# AtoVproject_16n_ALPS_V1_4_NL.net
KiCad netlist of a schematic drawn in EAGLE
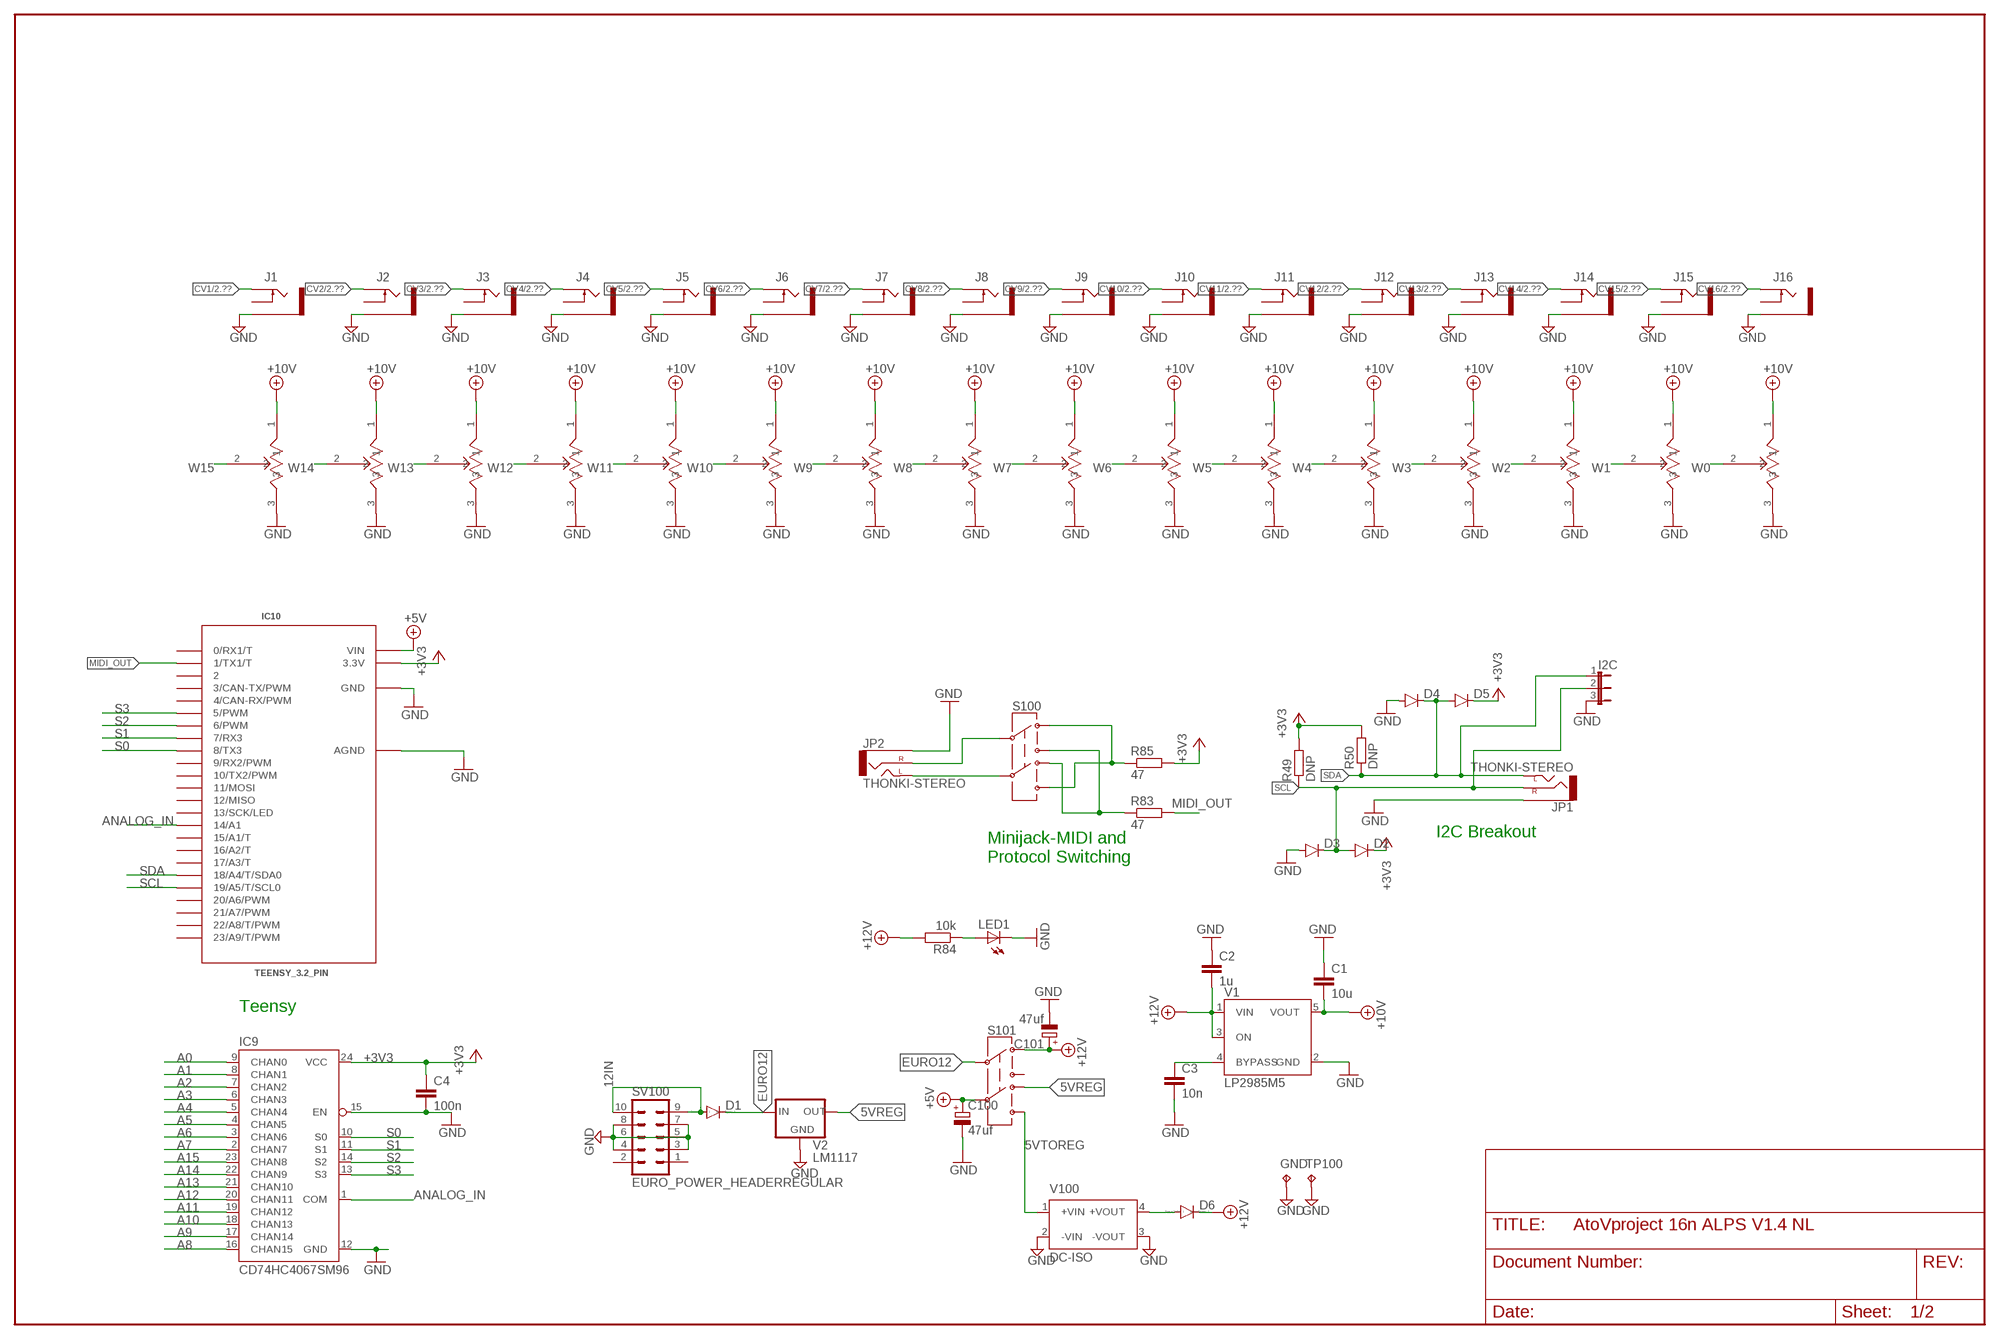
[diagram p0: schematic, sheet 1]
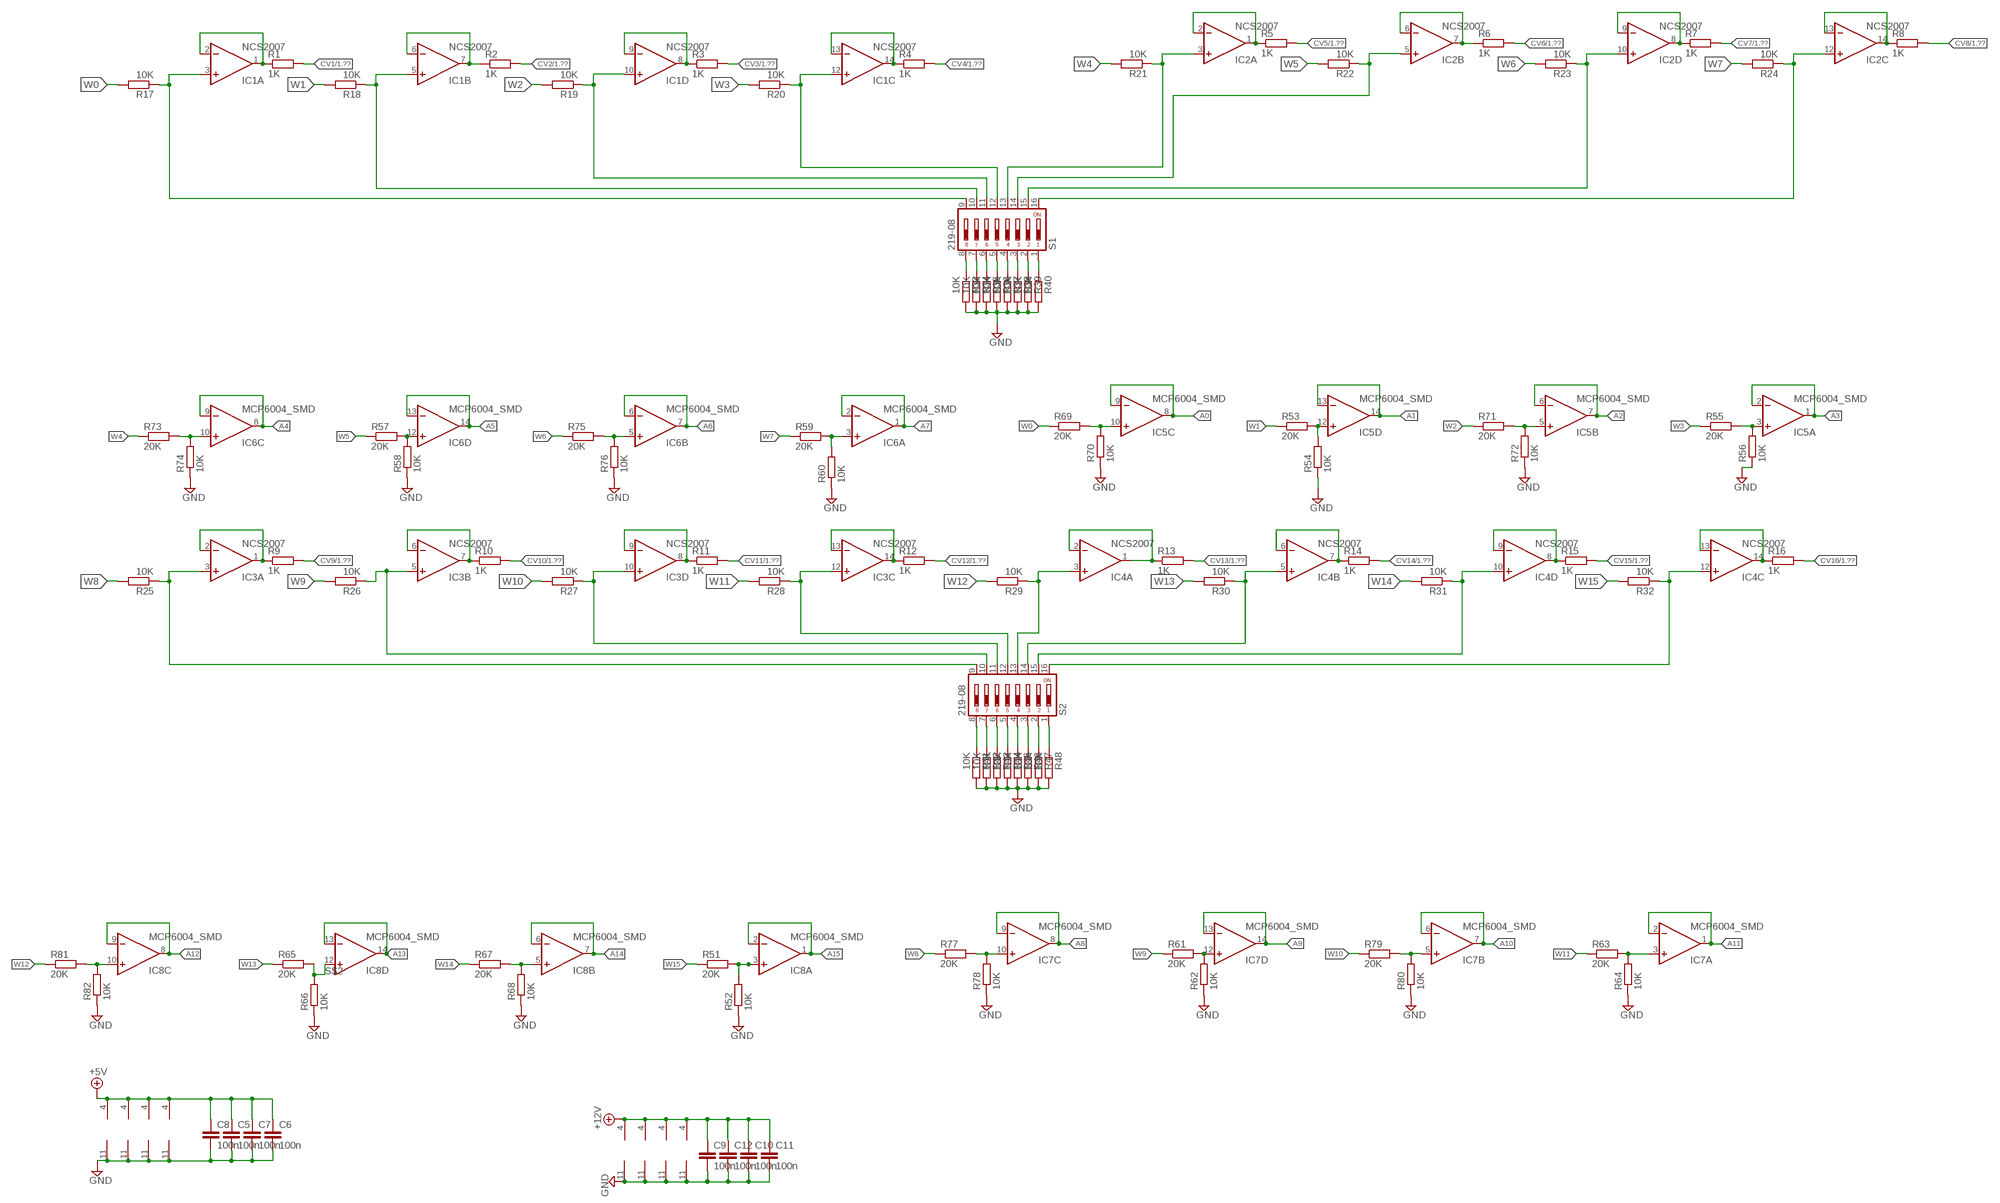
[diagram p1: schematic, sheet 2]

(export (version "E")
  (design (tool "Eeschema 10.0.6"))
  (components
    (comp (ref "C1")
      (value "10u")
      (footprint "eagle-import:C0805")
      (libsource (lib "eagle-import") (part "C-EUC0805"))
    )
    (comp (ref "C2")
      (value "1u")
      (footprint "eagle-import:C0805")
      (libsource (lib "eagle-import") (part "C-EUC0805"))
    )
    (comp (ref "C3")
      (value "10n")
      (footprint "eagle-import:C0805")
      (libsource (lib "eagle-import") (part "C-EUC0805"))
    )
    (comp (ref "C4")
      (value "100n")
      (footprint "eagle-import:C0805")
      (libsource (lib "eagle-import") (part "C-EUC0805"))
    )
    (comp (ref "C100")
      (value "47uf")
      (footprint "eagle-import:E2,5-6")
      (libsource (lib "eagle-import") (part "CPOL-EUE2.5-6"))
    )
    (comp (ref "C101")
      (value "47uf")
      (footprint "eagle-import:E2,5-6")
      (libsource (lib "eagle-import") (part "CPOL-EUE2.5-6"))
    )
    (comp (ref "D1")
      (value "DIODE-SOD123")
      (footprint "eagle-import:SOD123")
      (libsource (lib "eagle-import") (part "DIODE-SOD123"))
    )
    (comp (ref "D2")
      (value "DIODESOD123")
      (footprint "eagle-import:SOD-123")
      (libsource (lib "eagle-import") (part "DIODESOD123"))
    )
    (comp (ref "D3")
      (value "DIODESOD123")
      (footprint "eagle-import:SOD-123")
      (libsource (lib "eagle-import") (part "DIODESOD123"))
    )
    (comp (ref "D4")
      (value "DIODESOD123")
      (footprint "eagle-import:SOD-123")
      (libsource (lib "eagle-import") (part "DIODESOD123"))
    )
    (comp (ref "D5")
      (value "DIODESOD123")
      (footprint "eagle-import:SOD-123")
      (libsource (lib "eagle-import") (part "DIODESOD123"))
    )
    (comp (ref "D6")
      (value "DIODE-SOD123")
      (footprint "eagle-import:SOD123")
      (libsource (lib "eagle-import") (part "DIODE-SOD123"))
    )
    (comp (ref "GND")
      (value "TPPAD1-17")
      (footprint "eagle-import:P1-17")
      (libsource (lib "eagle-import") (part "TPPAD1-17"))
    )
    (comp (ref "I2C")
      (value "JP2E")
      (footprint "eagle-import:JP2")
      (libsource (lib "eagle-import") (part "JP2E"))
    )
    (comp (ref "IC9")
      (value "CD74HC4067SM96")
      (footprint "eagle-import:SOIC127P1030X265-24")
      (libsource (lib "eagle-import") (part "744067SO24"))
    )
    (comp (ref "IC10")
      (value "TEENSY_3.2_PIN")
      (footprint "eagle-import:TEENSY_3_AND_LC_SERIES_BOARDS_V1.4_TEENSY_3.0-3.2&LC_DIL")
      (libsource (lib "eagle-import") (part "TEENSY_3.2_PIN"))
    )
    (comp (ref "J1")
      (value "THONKICONN")
      (footprint "eagle-import:WQP-PJ301M-12JACK-BANANA")
      (libsource (lib "eagle-import") (part "THONKICONN"))
    )
    (comp (ref "J2")
      (value "THONKICONN")
      (footprint "eagle-import:WQP-PJ301M-12JACK-BANANA")
      (libsource (lib "eagle-import") (part "THONKICONN"))
    )
    (comp (ref "J3")
      (value "THONKICONN")
      (footprint "eagle-import:WQP-PJ301M-12JACK-BANANA")
      (libsource (lib "eagle-import") (part "THONKICONN"))
    )
    (comp (ref "J4")
      (value "THONKICONN")
      (footprint "eagle-import:WQP-PJ301M-12JACK-BANANA")
      (libsource (lib "eagle-import") (part "THONKICONN"))
    )
    (comp (ref "J5")
      (value "THONKICONN")
      (footprint "eagle-import:WQP-PJ301M-12JACK-BANANA")
      (libsource (lib "eagle-import") (part "THONKICONN"))
    )
    (comp (ref "J6")
      (value "THONKICONN")
      (footprint "eagle-import:WQP-PJ301M-12JACK-BANANA")
      (libsource (lib "eagle-import") (part "THONKICONN"))
    )
    (comp (ref "J7")
      (value "THONKICONN")
      (footprint "eagle-import:WQP-PJ301M-12JACK-BANANA")
      (libsource (lib "eagle-import") (part "THONKICONN"))
    )
    (comp (ref "J8")
      (value "THONKICONN")
      (footprint "eagle-import:WQP-PJ301M-12JACK-BANANA")
      (libsource (lib "eagle-import") (part "THONKICONN"))
    )
    (comp (ref "J9")
      (value "THONKICONN")
      (footprint "eagle-import:WQP-PJ301M-12JACK-BANANA")
      (libsource (lib "eagle-import") (part "THONKICONN"))
    )
    (comp (ref "J10")
      (value "THONKICONN")
      (footprint "eagle-import:WQP-PJ301M-12JACK-BANANA")
      (libsource (lib "eagle-import") (part "THONKICONN"))
    )
    (comp (ref "J11")
      (value "THONKICONN")
      (footprint "eagle-import:WQP-PJ301M-12JACK-BANANA")
      (libsource (lib "eagle-import") (part "THONKICONN"))
    )
    (comp (ref "J12")
      (value "THONKICONN")
      (footprint "eagle-import:WQP-PJ301M-12JACK-BANANA")
      (libsource (lib "eagle-import") (part "THONKICONN"))
    )
    (comp (ref "J13")
      (value "THONKICONN")
      (footprint "eagle-import:WQP-PJ301M-12JACK-BANANA")
      (libsource (lib "eagle-import") (part "THONKICONN"))
    )
    (comp (ref "J14")
      (value "THONKICONN")
      (footprint "eagle-import:WQP-PJ301M-12JACK-BANANA")
      (libsource (lib "eagle-import") (part "THONKICONN"))
    )
    (comp (ref "J15")
      (value "THONKICONN")
      (footprint "eagle-import:WQP-PJ301M-12JACK-BANANA")
      (libsource (lib "eagle-import") (part "THONKICONN"))
    )
    (comp (ref "J16")
      (value "THONKICONN")
      (footprint "eagle-import:WQP-PJ301M-12JACK-BANANA")
      (libsource (lib "eagle-import") (part "THONKICONN"))
    )
    (comp (ref "JP1")
      (value "THONKI-STEREO")
      (footprint "eagle-import:WQP-PJ366ST_JACK")
      (libsource (lib "eagle-import") (part "THONKI-STEREO"))
    )
    (comp (ref "JP2")
      (value "THONKI-STEREO")
      (footprint "eagle-import:WQP-PJ366ST_JACK")
      (libsource (lib "eagle-import") (part "THONKI-STEREO"))
    )
    (comp (ref "LED1")
      (value "LED")
      (footprint "eagle-import:LED3MM")
      (libsource (lib "eagle-import") (part "LED"))
    )
    (comp (ref "R49")
      (value "DNP")
      (footprint "eagle-import:R0805")
      (libsource (lib "eagle-import") (part "R-EU_R0805"))
    )
    (comp (ref "R50")
      (value "DNP")
      (footprint "eagle-import:R0805")
      (libsource (lib "eagle-import") (part "R-EU_R0805"))
    )
    (comp (ref "R83")
      (value "47")
      (footprint "eagle-import:R0805")
      (libsource (lib "eagle-import") (part "R-EU_R0805"))
    )
    (comp (ref "R84")
      (value "10k")
      (footprint "eagle-import:R0805")
      (libsource (lib "eagle-import") (part "R-EU_R0805"))
    )
    (comp (ref "R85")
      (value "47")
      (footprint "eagle-import:R0805")
      (libsource (lib "eagle-import") (part "R-EU_R0805"))
    )
    (comp (ref "S100")
      (value "SWITCH-DPDTEG2211")
      (footprint "eagle-import:EG2211")
      (libsource (lib "eagle-import") (part "SWITCH-DPDTEG2211"))
    )
    (comp (ref "S101")
      (value "SWITCH-DPDTEG2211")
      (footprint "eagle-import:EG2211")
      (libsource (lib "eagle-import") (part "SWITCH-DPDTEG2211"))
    )
    (comp (ref "SV100")
      (value "EURO_POWER_HEADERREGULAR")
      (footprint "eagle-import:EURO_POWER_HEADER")
      (libsource (lib "eagle-import") (part "EURO_POWER_HEADERREGULAR"))
    )
    (comp (ref "TP100")
      (value "TPPAD1-17")
      (footprint "eagle-import:P1-17")
      (libsource (lib "eagle-import") (part "TPPAD1-17"))
    )
    (comp (ref "U$1")
      (value "SLIDERSALPS-60MM")
      (footprint "eagle-import:MONOME_RS6011SP600")
      (libsource (lib "eagle-import") (part "SLIDERSALPS-60MM"))
    )
    (comp (ref "U$2")
      (value "SLIDERSALPS-60MM")
      (footprint "eagle-import:MONOME_RS6011SP600")
      (libsource (lib "eagle-import") (part "SLIDERSALPS-60MM"))
    )
    (comp (ref "U$3")
      (value "SLIDERSALPS-60MM")
      (footprint "eagle-import:MONOME_RS6011SP600")
      (libsource (lib "eagle-import") (part "SLIDERSALPS-60MM"))
    )
    (comp (ref "U$4")
      (value "SLIDERSALPS-60MM")
      (footprint "eagle-import:MONOME_RS6011SP600")
      (libsource (lib "eagle-import") (part "SLIDERSALPS-60MM"))
    )
    (comp (ref "U$5")
      (value "SLIDERSALPS-60MM")
      (footprint "eagle-import:MONOME_RS6011SP600")
      (libsource (lib "eagle-import") (part "SLIDERSALPS-60MM"))
    )
    (comp (ref "U$6")
      (value "SLIDERSALPS-60MM")
      (footprint "eagle-import:MONOME_RS6011SP600")
      (libsource (lib "eagle-import") (part "SLIDERSALPS-60MM"))
    )
    (comp (ref "U$7")
      (value "SLIDERSALPS-60MM")
      (footprint "eagle-import:MONOME_RS6011SP600")
      (libsource (lib "eagle-import") (part "SLIDERSALPS-60MM"))
    )
    (comp (ref "U$8")
      (value "SLIDERSALPS-60MM")
      (footprint "eagle-import:MONOME_RS6011SP600")
      (libsource (lib "eagle-import") (part "SLIDERSALPS-60MM"))
    )
    (comp (ref "U$9")
      (value "SLIDERSALPS-60MM")
      (footprint "eagle-import:MONOME_RS6011SP600")
      (libsource (lib "eagle-import") (part "SLIDERSALPS-60MM"))
    )
    (comp (ref "U$10")
      (value "SLIDERSALPS-60MM")
      (footprint "eagle-import:MONOME_RS6011SP600")
      (libsource (lib "eagle-import") (part "SLIDERSALPS-60MM"))
    )
    (comp (ref "U$11")
      (value "SLIDERSALPS-60MM")
      (footprint "eagle-import:MONOME_RS6011SP600")
      (libsource (lib "eagle-import") (part "SLIDERSALPS-60MM"))
    )
    (comp (ref "U$12")
      (value "SLIDERSALPS-60MM")
      (footprint "eagle-import:MONOME_RS6011SP600")
      (libsource (lib "eagle-import") (part "SLIDERSALPS-60MM"))
    )
    (comp (ref "U$13")
      (value "SLIDERSALPS-60MM")
      (footprint "eagle-import:MONOME_RS6011SP600")
      (libsource (lib "eagle-import") (part "SLIDERSALPS-60MM"))
    )
    (comp (ref "U$14")
      (value "SLIDERSALPS-60MM")
      (footprint "eagle-import:MONOME_RS6011SP600")
      (libsource (lib "eagle-import") (part "SLIDERSALPS-60MM"))
    )
    (comp (ref "U$15")
      (value "SLIDERSALPS-60MM")
      (footprint "eagle-import:MONOME_RS6011SP600")
      (libsource (lib "eagle-import") (part "SLIDERSALPS-60MM"))
    )
    (comp (ref "U$16")
      (value "SLIDERSALPS-60MM")
      (footprint "eagle-import:MONOME_RS6011SP600")
      (libsource (lib "eagle-import") (part "SLIDERSALPS-60MM"))
    )
    (comp (ref "V1")
      (value "LP2985M5")
      (footprint "eagle-import:SOT23-5")
      (libsource (lib "eagle-import") (part "LP2985M5"))
    )
    (comp (ref "V2")
      (value "LM1117")
      (footprint "eagle-import:SOT223")
      (libsource (lib "eagle-import") (part "LM1117"))
    )
    (comp (ref "V100")
      (value "DC-ISO")
      (footprint "eagle-import:TMA")
      (libsource (lib "eagle-import") (part "DC-ISO"))
    )
    (comp (ref "C5")
      (value "100n")
      (footprint "eagle-import:C0805")
      (libsource (lib "eagle-import") (part "C-EUC0805"))
    )
    (comp (ref "C6")
      (value "100n")
      (footprint "eagle-import:C0805")
      (libsource (lib "eagle-import") (part "C-EUC0805"))
    )
    (comp (ref "C7")
      (value "100n")
      (footprint "eagle-import:C0805")
      (libsource (lib "eagle-import") (part "C-EUC0805"))
    )
    (comp (ref "C8")
      (value "100n")
      (footprint "eagle-import:C0805")
      (libsource (lib "eagle-import") (part "C-EUC0805"))
    )
    (comp (ref "C9")
      (value "100n")
      (footprint "eagle-import:C0805")
      (libsource (lib "eagle-import") (part "C-EUC0805"))
    )
    (comp (ref "C10")
      (value "100n")
      (footprint "eagle-import:C0805")
      (libsource (lib "eagle-import") (part "C-EUC0805"))
    )
    (comp (ref "C11")
      (value "100n")
      (footprint "eagle-import:C0805")
      (libsource (lib "eagle-import") (part "C-EUC0805"))
    )
    (comp (ref "C12")
      (value "100n")
      (footprint "eagle-import:C0805")
      (libsource (lib "eagle-import") (part "C-EUC0805"))
    )
    (comp (ref "IC1")
      (value "NCS2007")
      (footprint "eagle-import:SO14")
      (libsource (lib "eagle-import") (part "TL074"))
    )
    (comp (ref "IC2")
      (value "NCS2007")
      (footprint "eagle-import:SO14")
      (libsource (lib "eagle-import") (part "TL074"))
    )
    (comp (ref "IC3")
      (value "NCS2007")
      (footprint "eagle-import:SO14")
      (libsource (lib "eagle-import") (part "TL074"))
    )
    (comp (ref "IC4")
      (value "NCS2007")
      (footprint "eagle-import:SO14")
      (libsource (lib "eagle-import") (part "TL074"))
    )
    (comp (ref "IC5")
      (value "MCP6004_SMD")
      (footprint "eagle-import:SO14")
      (libsource (lib "eagle-import") (part "MCP6004_SMD"))
    )
    (comp (ref "IC6")
      (value "MCP6004_SMD")
      (footprint "eagle-import:SO14")
      (libsource (lib "eagle-import") (part "MCP6004_SMD"))
    )
    (comp (ref "IC7")
      (value "MCP6004_SMD")
      (footprint "eagle-import:SO14")
      (libsource (lib "eagle-import") (part "MCP6004_SMD"))
    )
    (comp (ref "IC8")
      (value "MCP6004_SMD")
      (footprint "eagle-import:SO14")
      (libsource (lib "eagle-import") (part "MCP6004_SMD"))
    )
    (comp (ref "R1")
      (value "1K")
      (footprint "eagle-import:R0805")
      (libsource (lib "eagle-import") (part "R-EU_R0805"))
    )
    (comp (ref "R2")
      (value "1K")
      (footprint "eagle-import:R0805")
      (libsource (lib "eagle-import") (part "R-EU_R0805"))
    )
    (comp (ref "R3")
      (value "1K")
      (footprint "eagle-import:R0805")
      (libsource (lib "eagle-import") (part "R-EU_R0805"))
    )
    (comp (ref "R4")
      (value "1K")
      (footprint "eagle-import:R0805")
      (libsource (lib "eagle-import") (part "R-EU_R0805"))
    )
    (comp (ref "R5")
      (value "1K")
      (footprint "eagle-import:R0805")
      (libsource (lib "eagle-import") (part "R-EU_R0805"))
    )
    (comp (ref "R6")
      (value "1K")
      (footprint "eagle-import:R0805")
      (libsource (lib "eagle-import") (part "R-EU_R0805"))
    )
    (comp (ref "R7")
      (value "1K")
      (footprint "eagle-import:R0805")
      (libsource (lib "eagle-import") (part "R-EU_R0805"))
    )
    (comp (ref "R8")
      (value "1K")
      (footprint "eagle-import:R0805")
      (libsource (lib "eagle-import") (part "R-EU_R0805"))
    )
    (comp (ref "R9")
      (value "1K")
      (footprint "eagle-import:R0805")
      (libsource (lib "eagle-import") (part "R-EU_R0805"))
    )
    (comp (ref "R10")
      (value "1K")
      (footprint "eagle-import:R0805")
      (libsource (lib "eagle-import") (part "R-EU_R0805"))
    )
    (comp (ref "R11")
      (value "1K")
      (footprint "eagle-import:R0805")
      (libsource (lib "eagle-import") (part "R-EU_R0805"))
    )
    (comp (ref "R12")
      (value "1K")
      (footprint "eagle-import:R0805")
      (libsource (lib "eagle-import") (part "R-EU_R0805"))
    )
    (comp (ref "R13")
      (value "1K")
      (footprint "eagle-import:R0805")
      (libsource (lib "eagle-import") (part "R-EU_R0805"))
    )
    (comp (ref "R14")
      (value "1K")
      (footprint "eagle-import:R0805")
      (libsource (lib "eagle-import") (part "R-EU_R0805"))
    )
    (comp (ref "R15")
      (value "1K")
      (footprint "eagle-import:R0805")
      (libsource (lib "eagle-import") (part "R-EU_R0805"))
    )
    (comp (ref "R16")
      (value "1K")
      (footprint "eagle-import:R0805")
      (libsource (lib "eagle-import") (part "R-EU_R0805"))
    )
    (comp (ref "R17")
      (value "10K")
      (footprint "eagle-import:R0805")
      (libsource (lib "eagle-import") (part "R-EU_R0805"))
    )
    (comp (ref "R18")
      (value "10K")
      (footprint "eagle-import:R0805")
      (libsource (lib "eagle-import") (part "R-EU_R0805"))
    )
    (comp (ref "R19")
      (value "10K")
      (footprint "eagle-import:R0805")
      (libsource (lib "eagle-import") (part "R-EU_R0805"))
    )
    (comp (ref "R20")
      (value "10K")
      (footprint "eagle-import:R0805")
      (libsource (lib "eagle-import") (part "R-EU_R0805"))
    )
    (comp (ref "R21")
      (value "10K")
      (footprint "eagle-import:R0805")
      (libsource (lib "eagle-import") (part "R-EU_R0805"))
    )
    (comp (ref "R22")
      (value "10K")
      (footprint "eagle-import:R0805")
      (libsource (lib "eagle-import") (part "R-EU_R0805"))
    )
    (comp (ref "R23")
      (value "10K")
      (footprint "eagle-import:R0805")
      (libsource (lib "eagle-import") (part "R-EU_R0805"))
    )
    (comp (ref "R24")
      (value "10K")
      (footprint "eagle-import:R0805")
      (libsource (lib "eagle-import") (part "R-EU_R0805"))
    )
    (comp (ref "R25")
      (value "10K")
      (footprint "eagle-import:R0805")
      (libsource (lib "eagle-import") (part "R-EU_R0805"))
    )
    (comp (ref "R26")
      (value "10K")
      (footprint "eagle-import:R0805")
      (libsource (lib "eagle-import") (part "R-EU_R0805"))
    )
    (comp (ref "R27")
      (value "10K")
      (footprint "eagle-import:R0805")
      (libsource (lib "eagle-import") (part "R-EU_R0805"))
    )
    (comp (ref "R28")
      (value "10K")
      (footprint "eagle-import:R0805")
      (libsource (lib "eagle-import") (part "R-EU_R0805"))
    )
    (comp (ref "R29")
      (value "10K")
      (footprint "eagle-import:R0805")
      (libsource (lib "eagle-import") (part "R-EU_R0805"))
    )
    (comp (ref "R30")
      (value "10K")
      (footprint "eagle-import:R0805")
      (libsource (lib "eagle-import") (part "R-EU_R0805"))
    )
    (comp (ref "R31")
      (value "10K")
      (footprint "eagle-import:R0805")
      (libsource (lib "eagle-import") (part "R-EU_R0805"))
    )
    (comp (ref "R32")
      (value "10K")
      (footprint "eagle-import:R0805")
      (libsource (lib "eagle-import") (part "R-EU_R0805"))
    )
    (comp (ref "R33")
      (value "10K")
      (footprint "eagle-import:R0805")
      (libsource (lib "eagle-import") (part "R-EU_R0805"))
    )
    (comp (ref "R34")
      (value "10K")
      (footprint "eagle-import:R0805")
      (libsource (lib "eagle-import") (part "R-EU_R0805"))
    )
    (comp (ref "R35")
      (value "10K")
      (footprint "eagle-import:R0805")
      (libsource (lib "eagle-import") (part "R-EU_R0805"))
    )
    (comp (ref "R36")
      (value "10K")
      (footprint "eagle-import:R0805")
      (libsource (lib "eagle-import") (part "R-EU_R0805"))
    )
    (comp (ref "R37")
      (value "10K")
      (footprint "eagle-import:R0805")
      (libsource (lib "eagle-import") (part "R-EU_R0805"))
    )
    (comp (ref "R38")
      (value "10K")
      (footprint "eagle-import:R0805")
      (libsource (lib "eagle-import") (part "R-EU_R0805"))
    )
    (comp (ref "R39")
      (value "10K")
      (footprint "eagle-import:R0805")
      (libsource (lib "eagle-import") (part "R-EU_R0805"))
    )
    (comp (ref "R40")
      (value "10K")
      (footprint "eagle-import:R0805")
      (libsource (lib "eagle-import") (part "R-EU_R0805"))
    )
    (comp (ref "R41")
      (value "10K")
      (footprint "eagle-import:R0805")
      (libsource (lib "eagle-import") (part "R-EU_R0805"))
    )
    (comp (ref "R42")
      (value "10K")
      (footprint "eagle-import:R0805")
      (libsource (lib "eagle-import") (part "R-EU_R0805"))
    )
    (comp (ref "R43")
      (value "10K")
      (footprint "eagle-import:R0805")
      (libsource (lib "eagle-import") (part "R-EU_R0805"))
    )
    (comp (ref "R44")
      (value "10K")
      (footprint "eagle-import:R0805")
      (libsource (lib "eagle-import") (part "R-EU_R0805"))
    )
    (comp (ref "R45")
      (value "10K")
      (footprint "eagle-import:R0805")
      (libsource (lib "eagle-import") (part "R-EU_R0805"))
    )
    (comp (ref "R46")
      (value "10K")
      (footprint "eagle-import:R0805")
      (libsource (lib "eagle-import") (part "R-EU_R0805"))
    )
    (comp (ref "R47")
      (value "10K")
      (footprint "eagle-import:R0805")
      (libsource (lib "eagle-import") (part "R-EU_R0805"))
    )
    (comp (ref "R48")
      (value "10K")
      (footprint "eagle-import:R0805")
      (libsource (lib "eagle-import") (part "R-EU_R0805"))
    )
    (comp (ref "R51")
      (value "20K")
      (footprint "eagle-import:R0805")
      (libsource (lib "eagle-import") (part "R-EU_R0805"))
    )
    (comp (ref "R52")
      (value "10K")
      (footprint "eagle-import:R0805")
      (libsource (lib "eagle-import") (part "R-EU_R0805"))
    )
    (comp (ref "R53")
      (value "20K")
      (footprint "eagle-import:R0805")
      (libsource (lib "eagle-import") (part "R-EU_R0805"))
    )
    (comp (ref "R54")
      (value "10K")
      (footprint "eagle-import:R0805")
      (libsource (lib "eagle-import") (part "R-EU_R0805"))
    )
    (comp (ref "R55")
      (value "20K")
      (footprint "eagle-import:R0805")
      (libsource (lib "eagle-import") (part "R-EU_R0805"))
    )
    (comp (ref "R56")
      (value "10K")
      (footprint "eagle-import:R0805")
      (libsource (lib "eagle-import") (part "R-EU_R0805"))
    )
    (comp (ref "R57")
      (value "20K")
      (footprint "eagle-import:R0805")
      (libsource (lib "eagle-import") (part "R-EU_R0805"))
    )
    (comp (ref "R58")
      (value "10K")
      (footprint "eagle-import:R0805")
      (libsource (lib "eagle-import") (part "R-EU_R0805"))
    )
    (comp (ref "R59")
      (value "20K")
      (footprint "eagle-import:R0805")
      (libsource (lib "eagle-import") (part "R-EU_R0805"))
    )
    (comp (ref "R60")
      (value "10K")
      (footprint "eagle-import:R0805")
      (libsource (lib "eagle-import") (part "R-EU_R0805"))
    )
    (comp (ref "R61")
      (value "20K")
      (footprint "eagle-import:R0805")
      (libsource (lib "eagle-import") (part "R-EU_R0805"))
    )
    (comp (ref "R62")
      (value "10K")
      (footprint "eagle-import:R0805")
      (libsource (lib "eagle-import") (part "R-EU_R0805"))
    )
    (comp (ref "R63")
      (value "20K")
      (footprint "eagle-import:R0805")
      (libsource (lib "eagle-import") (part "R-EU_R0805"))
    )
    (comp (ref "R64")
      (value "10K")
      (footprint "eagle-import:R0805")
      (libsource (lib "eagle-import") (part "R-EU_R0805"))
    )
    (comp (ref "R65")
      (value "20K")
      (footprint "eagle-import:R0805")
      (libsource (lib "eagle-import") (part "R-EU_R0805"))
    )
    (comp (ref "R66")
      (value "10K")
      (footprint "eagle-import:R0805")
      (libsource (lib "eagle-import") (part "R-EU_R0805"))
    )
    (comp (ref "R67")
      (value "20K")
      (footprint "eagle-import:R0805")
      (libsource (lib "eagle-import") (part "R-EU_R0805"))
    )
    (comp (ref "R68")
      (value "10K")
      (footprint "eagle-import:R0805")
      (libsource (lib "eagle-import") (part "R-EU_R0805"))
    )
    (comp (ref "R69")
      (value "20K")
      (footprint "eagle-import:R0805")
      (libsource (lib "eagle-import") (part "R-EU_R0805"))
    )
    (comp (ref "R70")
      (value "10K")
      (footprint "eagle-import:R0805")
      (libsource (lib "eagle-import") (part "R-EU_R0805"))
    )
    (comp (ref "R71")
      (value "20K")
      (footprint "eagle-import:R0805")
      (libsource (lib "eagle-import") (part "R-EU_R0805"))
    )
    (comp (ref "R72")
      (value "10K")
      (footprint "eagle-import:R0805")
      (libsource (lib "eagle-import") (part "R-EU_R0805"))
    )
    (comp (ref "R73")
      (value "20K")
      (footprint "eagle-import:R0805")
      (libsource (lib "eagle-import") (part "R-EU_R0805"))
    )
    (comp (ref "R74")
      (value "10K")
      (footprint "eagle-import:R0805")
      (libsource (lib "eagle-import") (part "R-EU_R0805"))
    )
    (comp (ref "R75")
      (value "20K")
      (footprint "eagle-import:R0805")
      (libsource (lib "eagle-import") (part "R-EU_R0805"))
    )
    (comp (ref "R76")
      (value "10K")
      (footprint "eagle-import:R0805")
      (libsource (lib "eagle-import") (part "R-EU_R0805"))
    )
    (comp (ref "R77")
      (value "20K")
      (footprint "eagle-import:R0805")
      (libsource (lib "eagle-import") (part "R-EU_R0805"))
    )
    (comp (ref "R78")
      (value "10K")
      (footprint "eagle-import:R0805")
      (libsource (lib "eagle-import") (part "R-EU_R0805"))
    )
    (comp (ref "R79")
      (value "20K")
      (footprint "eagle-import:R0805")
      (libsource (lib "eagle-import") (part "R-EU_R0805"))
    )
    (comp (ref "R80")
      (value "10K")
      (footprint "eagle-import:R0805")
      (libsource (lib "eagle-import") (part "R-EU_R0805"))
    )
    (comp (ref "R81")
      (value "20K")
      (footprint "eagle-import:R0805")
      (libsource (lib "eagle-import") (part "R-EU_R0805"))
    )
    (comp (ref "R82")
      (value "10K")
      (footprint "eagle-import:R0805")
      (libsource (lib "eagle-import") (part "R-EU_R0805"))
    )
    (comp (ref "S1")
      (value "219-08")
      (footprint "eagle-import:CTS-219-08")
      (libsource (lib "eagle-import") (part "219-08"))
    )
    (comp (ref "S2")
      (value "219-08")
      (footprint "eagle-import:CTS-219-08")
      (libsource (lib "eagle-import") (part "219-08"))
    )
  )
  (nets
    (net (code "1") (name "+3V3") (class "Default")
      (node (ref "C4") (pin "1") (pinfunction "1_1") (pintype "passive"))
      (node (ref "D2") (pin "C") (pinfunction "C_C") (pintype "passive"))
      (node (ref "D5") (pin "C") (pinfunction "C_C") (pintype "passive"))
      (node (ref "IC10") (pin "3.3V") (pinfunction "3.3V_3.3V") (pintype "power_in"))
      (node (ref "IC9") (pin "24") (pinfunction "VCC_24") (pintype "bidirectional"))
      (node (ref "R49") (pin "2") (pinfunction "2_2") (pintype "passive"))
      (node (ref "R50") (pin "2") (pinfunction "2_2") (pintype "passive"))
      (node (ref "R85") (pin "2") (pinfunction "2_2") (pintype "passive"))
    )
    (net (code "2") (name "+5V") (class "Default")
      (node (ref "C100") (pin "+") (pinfunction "+_+") (pintype "passive"))
      (node (ref "C5") (pin "1") (pinfunction "1_1") (pintype "passive"))
      (node (ref "C6") (pin "1") (pinfunction "1_1") (pintype "passive"))
      (node (ref "C7") (pin "1") (pinfunction "1_1") (pintype "passive"))
      (node (ref "C8") (pin "1") (pinfunction "1_1") (pintype "passive"))
      (node (ref "IC10") (pin "VIN") (pinfunction "VIN_VIN") (pintype "power_in"))
      (node (ref "IC5") (pin "4") (pinfunction "V+_4") (pintype "power_in"))
      (node (ref "IC6") (pin "4") (pinfunction "V+_4") (pintype "power_in"))
      (node (ref "IC7") (pin "4") (pinfunction "V+_4") (pintype "power_in"))
      (node (ref "IC8") (pin "4") (pinfunction "V+_4") (pintype "power_in"))
      (node (ref "S101") (pin "P2") (pinfunction "5_P2") (pintype "bidirectional"))
    )
    (net (code "3") (name "+10V") (class "Default")
      (node (ref "C1") (pin "2") (pinfunction "2_2") (pintype "passive"))
      (node (ref "U$1") (pin "1") (pinfunction "1_1") (pintype "bidirectional"))
      (node (ref "U$10") (pin "1") (pinfunction "1_1") (pintype "bidirectional"))
      (node (ref "U$11") (pin "1") (pinfunction "1_1") (pintype "bidirectional"))
      (node (ref "U$12") (pin "1") (pinfunction "1_1") (pintype "bidirectional"))
      (node (ref "U$13") (pin "1") (pinfunction "1_1") (pintype "bidirectional"))
      (node (ref "U$14") (pin "1") (pinfunction "1_1") (pintype "bidirectional"))
      (node (ref "U$15") (pin "1") (pinfunction "1_1") (pintype "bidirectional"))
      (node (ref "U$16") (pin "1") (pinfunction "1_1") (pintype "bidirectional"))
      (node (ref "U$2") (pin "1") (pinfunction "1_1") (pintype "bidirectional"))
      (node (ref "U$3") (pin "1") (pinfunction "1_1") (pintype "bidirectional"))
      (node (ref "U$4") (pin "1") (pinfunction "1_1") (pintype "bidirectional"))
      (node (ref "U$5") (pin "1") (pinfunction "1_1") (pintype "bidirectional"))
      (node (ref "U$6") (pin "1") (pinfunction "1_1") (pintype "bidirectional"))
      (node (ref "U$7") (pin "1") (pinfunction "1_1") (pintype "bidirectional"))
      (node (ref "U$8") (pin "1") (pinfunction "1_1") (pintype "bidirectional"))
      (node (ref "U$9") (pin "1") (pinfunction "1_1") (pintype "bidirectional"))
      (node (ref "V1") (pin "5") (pinfunction "VOUT_5") (pintype "output"))
    )
    (net (code "4") (name "+12V") (class "Default")
      (node (ref "C10") (pin "1") (pinfunction "1_1") (pintype "passive"))
      (node (ref "C101") (pin "+") (pinfunction "+_+") (pintype "passive"))
      (node (ref "C11") (pin "1") (pinfunction "1_1") (pintype "passive"))
      (node (ref "C12") (pin "1") (pinfunction "1_1") (pintype "passive"))
      (node (ref "C2") (pin "2") (pinfunction "2_2") (pintype "passive"))
      (node (ref "C9") (pin "1") (pinfunction "1_1") (pintype "passive"))
      (node (ref "D6") (pin "C") (pinfunction "C_C") (pintype "passive"))
      (node (ref "IC1") (pin "4") (pinfunction "V+_4") (pintype "power_in"))
      (node (ref "IC2") (pin "4") (pinfunction "V+_4") (pintype "power_in"))
      (node (ref "IC3") (pin "4") (pinfunction "V+_4") (pintype "power_in"))
      (node (ref "IC4") (pin "4") (pinfunction "V+_4") (pintype "power_in"))
      (node (ref "R84") (pin "2") (pinfunction "2_2") (pintype "passive"))
      (node (ref "S101") (pin "P1-TA") (pinfunction "1_P1-TA") (pintype "bidirectional"))
      (node (ref "V1") (pin "1") (pinfunction "VIN_1") (pintype "power_in"))
      (node (ref "V1") (pin "3") (pinfunction "ON_3") (pintype "input"))
    )
    (net (code "5") (name "5VREG") (class "Default")
      (node (ref "S101") (pin "P2-TA") (pinfunction "4_P2-TA") (pintype "bidirectional"))
      (node (ref "V2") (pin "OUT") (pinfunction "OUT_OUT") (pintype "passive"))
      (node (ref "V2") (pin "TAB") (pinfunction "OUT_TAB") (pintype "passive"))
    )
    (net (code "6") (name "5VTOREG") (class "Default")
      (node (ref "S101") (pin "P2-TB") (pinfunction "6_P2-TB") (pintype "bidirectional"))
      (node (ref "V100") (pin "1") (pinfunction "+VIN_1") (pintype "passive"))
    )
    (net (code "7") (name "12IN") (class "Default")
      (node (ref "D1") (pin "A") (pinfunction "A_A") (pintype "passive"))
      (node (ref "SV100") (pin "10") (pinfunction "10_10") (pintype "passive"))
      (node (ref "SV100") (pin "9") (pinfunction "9_9") (pintype "passive"))
    )
    (net (code "8") (name "A0") (class "Default")
      (node (ref "IC5") (pin "8") (pinfunction "OUT_8") (pintype "output"))
      (node (ref "IC5") (pin "9") (pinfunction "-IN_9") (pintype "input"))
      (node (ref "IC9") (pin "9") (pinfunction "CHAN0_9") (pintype "bidirectional"))
    )
    (net (code "9") (name "A1") (class "Default")
      (node (ref "IC5") (pin "13") (pinfunction "-IN_13") (pintype "input"))
      (node (ref "IC5") (pin "14") (pinfunction "OUT_14") (pintype "output"))
      (node (ref "IC9") (pin "8") (pinfunction "CHAN1_8") (pintype "bidirectional"))
    )
    (net (code "10") (name "A2") (class "Default")
      (node (ref "IC5") (pin "6") (pinfunction "-IN_6") (pintype "input"))
      (node (ref "IC5") (pin "7") (pinfunction "OUT_7") (pintype "output"))
      (node (ref "IC9") (pin "7") (pinfunction "CHAN2_7") (pintype "bidirectional"))
    )
    (net (code "11") (name "A3") (class "Default")
      (node (ref "IC5") (pin "1") (pinfunction "OUT_1") (pintype "output"))
      (node (ref "IC5") (pin "2") (pinfunction "-IN_2") (pintype "input"))
      (node (ref "IC9") (pin "6") (pinfunction "CHAN3_6") (pintype "bidirectional"))
    )
    (net (code "12") (name "A4") (class "Default")
      (node (ref "IC6") (pin "8") (pinfunction "OUT_8") (pintype "output"))
      (node (ref "IC6") (pin "9") (pinfunction "-IN_9") (pintype "input"))
      (node (ref "IC9") (pin "5") (pinfunction "CHAN4_5") (pintype "bidirectional"))
    )
    (net (code "13") (name "A5") (class "Default")
      (node (ref "IC6") (pin "13") (pinfunction "-IN_13") (pintype "input"))
      (node (ref "IC6") (pin "14") (pinfunction "OUT_14") (pintype "output"))
      (node (ref "IC9") (pin "4") (pinfunction "CHAN5_4") (pintype "bidirectional"))
    )
    (net (code "14") (name "A6") (class "Default")
      (node (ref "IC6") (pin "6") (pinfunction "-IN_6") (pintype "input"))
      (node (ref "IC6") (pin "7") (pinfunction "OUT_7") (pintype "output"))
      (node (ref "IC9") (pin "3") (pinfunction "CHAN6_3") (pintype "bidirectional"))
    )
    (net (code "15") (name "A7") (class "Default")
      (node (ref "IC6") (pin "1") (pinfunction "OUT_1") (pintype "output"))
      (node (ref "IC6") (pin "2") (pinfunction "-IN_2") (pintype "input"))
      (node (ref "IC9") (pin "2") (pinfunction "CHAN7_2") (pintype "bidirectional"))
    )
    (net (code "16") (name "A8") (class "Default")
      (node (ref "IC7") (pin "8") (pinfunction "OUT_8") (pintype "output"))
      (node (ref "IC7") (pin "9") (pinfunction "-IN_9") (pintype "input"))
      (node (ref "IC9") (pin "16") (pinfunction "CHAN15_16") (pintype "bidirectional"))
    )
    (net (code "17") (name "A9") (class "Default")
      (node (ref "IC7") (pin "13") (pinfunction "-IN_13") (pintype "input"))
      (node (ref "IC7") (pin "14") (pinfunction "OUT_14") (pintype "output"))
      (node (ref "IC9") (pin "17") (pinfunction "CHAN14_17") (pintype "bidirectional"))
    )
    (net (code "18") (name "A10") (class "Default")
      (node (ref "IC7") (pin "6") (pinfunction "-IN_6") (pintype "input"))
      (node (ref "IC7") (pin "7") (pinfunction "OUT_7") (pintype "output"))
      (node (ref "IC9") (pin "18") (pinfunction "CHAN13_18") (pintype "bidirectional"))
    )
    (net (code "19") (name "A11") (class "Default")
      (node (ref "IC7") (pin "1") (pinfunction "OUT_1") (pintype "output"))
      (node (ref "IC7") (pin "2") (pinfunction "-IN_2") (pintype "input"))
      (node (ref "IC9") (pin "19") (pinfunction "CHAN12_19") (pintype "bidirectional"))
    )
    (net (code "20") (name "A12") (class "Default")
      (node (ref "IC8") (pin "8") (pinfunction "OUT_8") (pintype "output"))
      (node (ref "IC8") (pin "9") (pinfunction "-IN_9") (pintype "input"))
      (node (ref "IC9") (pin "20") (pinfunction "CHAN11_20") (pintype "bidirectional"))
    )
    (net (code "21") (name "A13") (class "Default")
      (node (ref "IC8") (pin "13") (pinfunction "-IN_13") (pintype "input"))
      (node (ref "IC8") (pin "14") (pinfunction "OUT_14") (pintype "output"))
      (node (ref "IC9") (pin "21") (pinfunction "CHAN10_21") (pintype "bidirectional"))
    )
    (net (code "22") (name "A14") (class "Default")
      (node (ref "IC8") (pin "6") (pinfunction "-IN_6") (pintype "input"))
      (node (ref "IC8") (pin "7") (pinfunction "OUT_7") (pintype "output"))
      (node (ref "IC9") (pin "22") (pinfunction "CHAN9_22") (pintype "bidirectional"))
    )
    (net (code "23") (name "A15") (class "Default")
      (node (ref "IC8") (pin "1") (pinfunction "OUT_1") (pintype "output"))
      (node (ref "IC8") (pin "2") (pinfunction "-IN_2") (pintype "input"))
      (node (ref "IC9") (pin "23") (pinfunction "CHAN8_23") (pintype "bidirectional"))
    )
    (net (code "24") (name "ANALOG_IN") (class "Default")
      (node (ref "IC10") (pin "14/A0") (pinfunction "14/A1_14/A0") (pintype "bidirectional"))
      (node (ref "IC9") (pin "1") (pinfunction "COM_1") (pintype "bidirectional"))
    )
    (net (code "25") (name "CV1") (class "Default")
      (node (ref "J1") (pin "P$1_TIP") (pinfunction "TIP_P$1_TIP") (pintype "passive"))
      (node (ref "R1") (pin "2") (pinfunction "2_2") (pintype "passive"))
    )
    (net (code "26") (name "CV2") (class "Default")
      (node (ref "J2") (pin "P$1_TIP") (pinfunction "TIP_P$1_TIP") (pintype "passive"))
      (node (ref "R2") (pin "2") (pinfunction "2_2") (pintype "passive"))
    )
    (net (code "27") (name "CV3") (class "Default")
      (node (ref "J3") (pin "P$1_TIP") (pinfunction "TIP_P$1_TIP") (pintype "passive"))
      (node (ref "R3") (pin "2") (pinfunction "2_2") (pintype "passive"))
    )
    (net (code "28") (name "CV4") (class "Default")
      (node (ref "J4") (pin "P$1_TIP") (pinfunction "TIP_P$1_TIP") (pintype "passive"))
      (node (ref "R4") (pin "2") (pinfunction "2_2") (pintype "passive"))
    )
    (net (code "29") (name "CV5") (class "Default")
      (node (ref "J5") (pin "P$1_TIP") (pinfunction "TIP_P$1_TIP") (pintype "passive"))
      (node (ref "R5") (pin "2") (pinfunction "2_2") (pintype "passive"))
    )
    (net (code "30") (name "CV6") (class "Default")
      (node (ref "J6") (pin "P$1_TIP") (pinfunction "TIP_P$1_TIP") (pintype "passive"))
      (node (ref "R6") (pin "2") (pinfunction "2_2") (pintype "passive"))
    )
    (net (code "31") (name "CV7") (class "Default")
      (node (ref "J7") (pin "P$1_TIP") (pinfunction "TIP_P$1_TIP") (pintype "passive"))
      (node (ref "R7") (pin "2") (pinfunction "2_2") (pintype "passive"))
    )
    (net (code "32") (name "CV8") (class "Default")
      (node (ref "J8") (pin "P$1_TIP") (pinfunction "TIP_P$1_TIP") (pintype "passive"))
      (node (ref "R8") (pin "2") (pinfunction "2_2") (pintype "passive"))
    )
    (net (code "33") (name "CV9") (class "Default")
      (node (ref "J9") (pin "P$1_TIP") (pinfunction "TIP_P$1_TIP") (pintype "passive"))
      (node (ref "R9") (pin "2") (pinfunction "2_2") (pintype "passive"))
    )
    (net (code "34") (name "CV10") (class "Default")
      (node (ref "J10") (pin "P$1_TIP") (pinfunction "TIP_P$1_TIP") (pintype "passive"))
      (node (ref "R10") (pin "2") (pinfunction "2_2") (pintype "passive"))
    )
    (net (code "35") (name "CV11") (class "Default")
      (node (ref "J11") (pin "P$1_TIP") (pinfunction "TIP_P$1_TIP") (pintype "passive"))
      (node (ref "R11") (pin "2") (pinfunction "2_2") (pintype "passive"))
    )
    (net (code "36") (name "CV12") (class "Default")
      (node (ref "J12") (pin "P$1_TIP") (pinfunction "TIP_P$1_TIP") (pintype "passive"))
      (node (ref "R12") (pin "2") (pinfunction "2_2") (pintype "passive"))
    )
    (net (code "37") (name "CV13") (class "Default")
      (node (ref "J13") (pin "P$1_TIP") (pinfunction "TIP_P$1_TIP") (pintype "passive"))
      (node (ref "R13") (pin "2") (pinfunction "2_2") (pintype "passive"))
    )
    (net (code "38") (name "CV14") (class "Default")
      (node (ref "J14") (pin "P$1_TIP") (pinfunction "TIP_P$1_TIP") (pintype "passive"))
      (node (ref "R14") (pin "2") (pinfunction "2_2") (pintype "passive"))
    )
    (net (code "39") (name "CV15") (class "Default")
      (node (ref "J15") (pin "P$1_TIP") (pinfunction "TIP_P$1_TIP") (pintype "passive"))
      (node (ref "R15") (pin "2") (pinfunction "2_2") (pintype "passive"))
    )
    (net (code "40") (name "CV16") (class "Default")
      (node (ref "J16") (pin "P$1_TIP") (pinfunction "TIP_P$1_TIP") (pintype "passive"))
      (node (ref "R16") (pin "2") (pinfunction "2_2") (pintype "passive"))
    )
    (net (code "41") (name "EURO12") (class "Default")
      (node (ref "D1") (pin "C") (pinfunction "C_C") (pintype "passive"))
      (node (ref "S101") (pin "P1") (pinfunction "2_P1") (pintype "bidirectional"))
      (node (ref "V2") (pin "IN") (pinfunction "IN_IN") (pintype "input"))
    )
    (net (code "42") (name "GND") (class "Default")
      (node (ref "C1") (pin "1") (pinfunction "1_1") (pintype "passive"))
      (node (ref "C10") (pin "2") (pinfunction "2_2") (pintype "passive"))
      (node (ref "C100") (pin "-") (pinfunction "-_-") (pintype "passive"))
      (node (ref "C101") (pin "-") (pinfunction "-_-") (pintype "passive"))
      (node (ref "C11") (pin "2") (pinfunction "2_2") (pintype "passive"))
      (node (ref "C12") (pin "2") (pinfunction "2_2") (pintype "passive"))
      (node (ref "C2") (pin "1") (pinfunction "1_1") (pintype "passive"))
      (node (ref "C3") (pin "2") (pinfunction "2_2") (pintype "passive"))
      (node (ref "C4") (pin "2") (pinfunction "2_2") (pintype "passive"))
      (node (ref "C5") (pin "2") (pinfunction "2_2") (pintype "passive"))
      (node (ref "C6") (pin "2") (pinfunction "2_2") (pintype "passive"))
      (node (ref "C7") (pin "2") (pinfunction "2_2") (pintype "passive"))
      (node (ref "C8") (pin "2") (pinfunction "2_2") (pintype "passive"))
      (node (ref "C9") (pin "2") (pinfunction "2_2") (pintype "passive"))
      (node (ref "D3") (pin "A") (pinfunction "A_A") (pintype "passive"))
      (node (ref "D4") (pin "A") (pinfunction "A_A") (pintype "passive"))
      (node (ref "GND") (pin "TP") (pinfunction "TP_TP") (pintype "input"))
      (node (ref "I2C") (pin "3") (pinfunction "3_3") (pintype "passive"))
      (node (ref "IC1") (pin "11") (pinfunction "V-_11") (pintype "power_in"))
      (node (ref "IC10") (pin "AGND") (pinfunction "AGND_AGND") (pintype "power_in"))
      (node (ref "IC10") (pin "GND") (pinfunction "GND_GND") (pintype "power_in"))
      (node (ref "IC2") (pin "11") (pinfunction "V-_11") (pintype "power_in"))
      (node (ref "IC3") (pin "11") (pinfunction "V-_11") (pintype "power_in"))
      (node (ref "IC4") (pin "11") (pinfunction "V-_11") (pintype "power_in"))
      (node (ref "IC5") (pin "11") (pinfunction "V-_11") (pintype "power_in"))
      (node (ref "IC6") (pin "11") (pinfunction "V-_11") (pintype "power_in"))
      (node (ref "IC7") (pin "11") (pinfunction "V-_11") (pintype "power_in"))
      (node (ref "IC8") (pin "11") (pinfunction "V-_11") (pintype "power_in"))
      (node (ref "IC9") (pin "12") (pinfunction "GND_12") (pintype "bidirectional"))
      (node (ref "IC9") (pin "15") (pinfunction "EN_15") (pintype "input"))
      (node (ref "J1") (pin "P$3_SLEEVE") (pinfunction "SLEEVE_P$3_SLEEVE") (pintype "passive"))
      (node (ref "J10") (pin "P$3_SLEEVE") (pinfunction "SLEEVE_P$3_SLEEVE") (pintype "passive"))
      (node (ref "J11") (pin "P$3_SLEEVE") (pinfunction "SLEEVE_P$3_SLEEVE") (pintype "passive"))
      (node (ref "J12") (pin "P$3_SLEEVE") (pinfunction "SLEEVE_P$3_SLEEVE") (pintype "passive"))
      (node (ref "J13") (pin "P$3_SLEEVE") (pinfunction "SLEEVE_P$3_SLEEVE") (pintype "passive"))
      (node (ref "J14") (pin "P$3_SLEEVE") (pinfunction "SLEEVE_P$3_SLEEVE") (pintype "passive"))
      (node (ref "J15") (pin "P$3_SLEEVE") (pinfunction "SLEEVE_P$3_SLEEVE") (pintype "passive"))
      (node (ref "J16") (pin "P$3_SLEEVE") (pinfunction "SLEEVE_P$3_SLEEVE") (pintype "passive"))
      (node (ref "J2") (pin "P$3_SLEEVE") (pinfunction "SLEEVE_P$3_SLEEVE") (pintype "passive"))
      (node (ref "J3") (pin "P$3_SLEEVE") (pinfunction "SLEEVE_P$3_SLEEVE") (pintype "passive"))
      (node (ref "J4") (pin "P$3_SLEEVE") (pinfunction "SLEEVE_P$3_SLEEVE") (pintype "passive"))
      (node (ref "J5") (pin "P$3_SLEEVE") (pinfunction "SLEEVE_P$3_SLEEVE") (pintype "passive"))
      (node (ref "J6") (pin "P$3_SLEEVE") (pinfunction "SLEEVE_P$3_SLEEVE") (pintype "passive"))
      (node (ref "J7") (pin "P$3_SLEEVE") (pinfunction "SLEEVE_P$3_SLEEVE") (pintype "passive"))
      (node (ref "J8") (pin "P$3_SLEEVE") (pinfunction "SLEEVE_P$3_SLEEVE") (pintype "passive"))
      (node (ref "J9") (pin "P$3_SLEEVE") (pinfunction "SLEEVE_P$3_SLEEVE") (pintype "passive"))
      (node (ref "JP1") (pin "P$3_SLEEVE") (pinfunction "SLEEVE_P$3_SLEEVE") (pintype "bidirectional"))
      (node (ref "JP2") (pin "P$3_SLEEVE") (pinfunction "SLEEVE_P$3_SLEEVE") (pintype "bidirectional"))
      (node (ref "LED1") (pin "K") (pinfunction "C_K") (pintype "passive"))
      (node (ref "R33") (pin "2") (pinfunction "2_2") (pintype "passive"))
      (node (ref "R34") (pin "2") (pinfunction "2_2") (pintype "passive"))
      (node (ref "R35") (pin "2") (pinfunction "2_2") (pintype "passive"))
      (node (ref "R36") (pin "2") (pinfunction "2_2") (pintype "passive"))
      (node (ref "R37") (pin "2") (pinfunction "2_2") (pintype "passive"))
      (node (ref "R38") (pin "2") (pinfunction "2_2") (pintype "passive"))
      (node (ref "R39") (pin "2") (pinfunction "2_2") (pintype "passive"))
      (node (ref "R40") (pin "2") (pinfunction "2_2") (pintype "passive"))
      (node (ref "R41") (pin "2") (pinfunction "2_2") (pintype "passive"))
      (node (ref "R42") (pin "2") (pinfunction "2_2") (pintype "passive"))
      (node (ref "R43") (pin "2") (pinfunction "2_2") (pintype "passive"))
      (node (ref "R44") (pin "2") (pinfunction "2_2") (pintype "passive"))
      (node (ref "R45") (pin "2") (pinfunction "2_2") (pintype "passive"))
      (node (ref "R46") (pin "2") (pinfunction "2_2") (pintype "passive"))
      (node (ref "R47") (pin "2") (pinfunction "2_2") (pintype "passive"))
      (node (ref "R48") (pin "2") (pinfunction "2_2") (pintype "passive"))
      (node (ref "R52") (pin "1") (pinfunction "1_1") (pintype "passive"))
      (node (ref "R54") (pin "1") (pinfunction "1_1") (pintype "passive"))
      (node (ref "R56") (pin "1") (pinfunction "1_1") (pintype "passive"))
      (node (ref "R58") (pin "1") (pinfunction "1_1") (pintype "passive"))
      (node (ref "R60") (pin "1") (pinfunction "1_1") (pintype "passive"))
      (node (ref "R62") (pin "1") (pinfunction "1_1") (pintype "passive"))
      (node (ref "R64") (pin "1") (pinfunction "1_1") (pintype "passive"))
      (node (ref "R66") (pin "1") (pinfunction "1_1") (pintype "passive"))
      (node (ref "R68") (pin "1") (pinfunction "1_1") (pintype "passive"))
      (node (ref "R70") (pin "1") (pinfunction "1_1") (pintype "passive"))
      (node (ref "R72") (pin "1") (pinfunction "1_1") (pintype "passive"))
      (node (ref "R74") (pin "1") (pinfunction "1_1") (pintype "passive"))
      (node (ref "R76") (pin "1") (pinfunction "1_1") (pintype "passive"))
      (node (ref "R78") (pin "1") (pinfunction "1_1") (pintype "passive"))
      (node (ref "R80") (pin "1") (pinfunction "1_1") (pintype "passive"))
      (node (ref "R82") (pin "1") (pinfunction "1_1") (pintype "passive"))
      (node (ref "SV100") (pin "3") (pinfunction "3_3") (pintype "passive"))
      (node (ref "SV100") (pin "4") (pinfunction "4_4") (pintype "passive"))
      (node (ref "SV100") (pin "5") (pinfunction "5_5") (pintype "passive"))
      (node (ref "SV100") (pin "6") (pinfunction "6_6") (pintype "passive"))
      (node (ref "SV100") (pin "7") (pinfunction "7_7") (pintype "passive"))
      (node (ref "SV100") (pin "8") (pinfunction "8_8") (pintype "passive"))
      (node (ref "TP100") (pin "TP") (pinfunction "TP_TP") (pintype "input"))
      (node (ref "U$1") (pin "3") (pinfunction "3_3") (pintype "bidirectional"))
      (node (ref "U$10") (pin "3") (pinfunction "3_3") (pintype "bidirectional"))
      (node (ref "U$11") (pin "3") (pinfunction "3_3") (pintype "bidirectional"))
      (node (ref "U$12") (pin "3") (pinfunction "3_3") (pintype "bidirectional"))
      (node (ref "U$13") (pin "3") (pinfunction "3_3") (pintype "bidirectional"))
      (node (ref "U$14") (pin "3") (pinfunction "3_3") (pintype "bidirectional"))
      (node (ref "U$15") (pin "3") (pinfunction "3_3") (pintype "bidirectional"))
      (node (ref "U$16") (pin "3") (pinfunction "3_3") (pintype "bidirectional"))
      (node (ref "U$2") (pin "3") (pinfunction "3_3") (pintype "bidirectional"))
      (node (ref "U$3") (pin "3") (pinfunction "3_3") (pintype "bidirectional"))
      (node (ref "U$4") (pin "3") (pinfunction "3_3") (pintype "bidirectional"))
      (node (ref "U$5") (pin "3") (pinfunction "3_3") (pintype "bidirectional"))
      (node (ref "U$6") (pin "3") (pinfunction "3_3") (pintype "bidirectional"))
      (node (ref "U$7") (pin "3") (pinfunction "3_3") (pintype "bidirectional"))
      (node (ref "U$8") (pin "3") (pinfunction "3_3") (pintype "bidirectional"))
      (node (ref "U$9") (pin "3") (pinfunction "3_3") (pintype "bidirectional"))
      (node (ref "V1") (pin "2") (pinfunction "GND_2") (pintype "power_in"))
      (node (ref "V100") (pin "2") (pinfunction "-VIN_2") (pintype "passive"))
      (node (ref "V100") (pin "3") (pinfunction "-VOUT_3") (pintype "passive"))
      (node (ref "V2") (pin "GND") (pinfunction "GND_GND") (pintype "input"))
    )
    (net (code "43") (name "MIDI_OUT") (class "Default")
      (node (ref "IC10") (pin "1") (pinfunction "1/TX1/T_1") (pintype "bidirectional"))
      (node (ref "R83") (pin "2") (pinfunction "2_2") (pintype "passive"))
    )
    (net (code "44") (name "Net-(IC1A-+IN)") (class "Default")
      (node (ref "IC1") (pin "3") (pinfunction "+IN_3") (pintype "input"))
      (node (ref "R17") (pin "1") (pinfunction "1_1") (pintype "passive"))
      (node (ref "S1") (pin "9") (pinfunction "9_9") (pintype "passive"))
    )
    (net (code "45") (name "Net-(IC1A--IN)") (class "Default")
      (node (ref "IC1") (pin "1") (pinfunction "OUT_1") (pintype "output"))
      (node (ref "IC1") (pin "2") (pinfunction "-IN_2") (pintype "input"))
      (node (ref "R1") (pin "1") (pinfunction "1_1") (pintype "passive"))
    )
    (net (code "46") (name "Net-(IC1B-+IN)") (class "Default")
      (node (ref "IC1") (pin "5") (pinfunction "+IN_5") (pintype "input"))
      (node (ref "R18") (pin "1") (pinfunction "1_1") (pintype "passive"))
      (node (ref "S1") (pin "10") (pinfunction "10_10") (pintype "passive"))
    )
    (net (code "47") (name "Net-(IC1B--IN)") (class "Default")
      (node (ref "IC1") (pin "6") (pinfunction "-IN_6") (pintype "input"))
      (node (ref "IC1") (pin "7") (pinfunction "OUT_7") (pintype "output"))
      (node (ref "R2") (pin "1") (pinfunction "1_1") (pintype "passive"))
    )
    (net (code "48") (name "Net-(IC1C-+IN)") (class "Default")
      (node (ref "IC1") (pin "12") (pinfunction "+IN_12") (pintype "input"))
      (node (ref "R20") (pin "1") (pinfunction "1_1") (pintype "passive"))
      (node (ref "S1") (pin "12") (pinfunction "12_12") (pintype "passive"))
    )
    (net (code "49") (name "Net-(IC1C--IN)") (class "Default")
      (node (ref "IC1") (pin "13") (pinfunction "-IN_13") (pintype "input"))
      (node (ref "IC1") (pin "14") (pinfunction "OUT_14") (pintype "output"))
      (node (ref "R4") (pin "1") (pinfunction "1_1") (pintype "passive"))
    )
    (net (code "50") (name "Net-(IC1D-+IN)") (class "Default")
      (node (ref "IC1") (pin "10") (pinfunction "+IN_10") (pintype "input"))
      (node (ref "R19") (pin "1") (pinfunction "1_1") (pintype "passive"))
      (node (ref "S1") (pin "11") (pinfunction "11_11") (pintype "passive"))
    )
    (net (code "51") (name "Net-(IC1D--IN)") (class "Default")
      (node (ref "IC1") (pin "8") (pinfunction "OUT_8") (pintype "output"))
      (node (ref "IC1") (pin "9") (pinfunction "-IN_9") (pintype "input"))
      (node (ref "R3") (pin "1") (pinfunction "1_1") (pintype "passive"))
    )
    (net (code "52") (name "Net-(IC2A-+IN)") (class "Default")
      (node (ref "IC2") (pin "3") (pinfunction "+IN_3") (pintype "input"))
      (node (ref "R21") (pin "1") (pinfunction "1_1") (pintype "passive"))
      (node (ref "S1") (pin "13") (pinfunction "13_13") (pintype "passive"))
    )
    (net (code "53") (name "Net-(IC2A--IN)") (class "Default")
      (node (ref "IC2") (pin "1") (pinfunction "OUT_1") (pintype "output"))
      (node (ref "IC2") (pin "2") (pinfunction "-IN_2") (pintype "input"))
      (node (ref "R5") (pin "1") (pinfunction "1_1") (pintype "passive"))
    )
    (net (code "54") (name "Net-(IC2B-+IN)") (class "Default")
      (node (ref "IC2") (pin "5") (pinfunction "+IN_5") (pintype "input"))
      (node (ref "R22") (pin "1") (pinfunction "1_1") (pintype "passive"))
      (node (ref "S1") (pin "14") (pinfunction "14_14") (pintype "passive"))
    )
    (net (code "55") (name "Net-(IC2B--IN)") (class "Default")
      (node (ref "IC2") (pin "6") (pinfunction "-IN_6") (pintype "input"))
      (node (ref "IC2") (pin "7") (pinfunction "OUT_7") (pintype "output"))
      (node (ref "R6") (pin "1") (pinfunction "1_1") (pintype "passive"))
    )
    (net (code "56") (name "Net-(IC2C-+IN)") (class "Default")
      (node (ref "IC2") (pin "12") (pinfunction "+IN_12") (pintype "input"))
      (node (ref "R24") (pin "1") (pinfunction "1_1") (pintype "passive"))
      (node (ref "S1") (pin "16") (pinfunction "16_16") (pintype "passive"))
    )
    (net (code "57") (name "Net-(IC2C--IN)") (class "Default")
      (node (ref "IC2") (pin "13") (pinfunction "-IN_13") (pintype "input"))
      (node (ref "IC2") (pin "14") (pinfunction "OUT_14") (pintype "output"))
      (node (ref "R8") (pin "1") (pinfunction "1_1") (pintype "passive"))
    )
    (net (code "58") (name "Net-(IC2D-+IN)") (class "Default")
      (node (ref "IC2") (pin "10") (pinfunction "+IN_10") (pintype "input"))
      (node (ref "R23") (pin "1") (pinfunction "1_1") (pintype "passive"))
      (node (ref "S1") (pin "15") (pinfunction "15_15") (pintype "passive"))
    )
    (net (code "59") (name "Net-(IC2D--IN)") (class "Default")
      (node (ref "IC2") (pin "8") (pinfunction "OUT_8") (pintype "output"))
      (node (ref "IC2") (pin "9") (pinfunction "-IN_9") (pintype "input"))
      (node (ref "R7") (pin "1") (pinfunction "1_1") (pintype "passive"))
    )
    (net (code "60") (name "Net-(IC3A-+IN)") (class "Default")
      (node (ref "IC3") (pin "3") (pinfunction "+IN_3") (pintype "input"))
      (node (ref "R25") (pin "1") (pinfunction "1_1") (pintype "passive"))
      (node (ref "S2") (pin "9") (pinfunction "9_9") (pintype "passive"))
    )
    (net (code "61") (name "Net-(IC3A--IN)") (class "Default")
      (node (ref "IC3") (pin "1") (pinfunction "OUT_1") (pintype "output"))
      (node (ref "IC3") (pin "2") (pinfunction "-IN_2") (pintype "input"))
      (node (ref "R9") (pin "1") (pinfunction "1_1") (pintype "passive"))
    )
    (net (code "62") (name "Net-(IC3B-+IN)") (class "Default")
      (node (ref "IC3") (pin "5") (pinfunction "+IN_5") (pintype "input"))
      (node (ref "R26") (pin "1") (pinfunction "1_1") (pintype "passive"))
      (node (ref "S2") (pin "10") (pinfunction "10_10") (pintype "passive"))
    )
    (net (code "63") (name "Net-(IC3B--IN)") (class "Default")
      (node (ref "IC3") (pin "6") (pinfunction "-IN_6") (pintype "input"))
      (node (ref "IC3") (pin "7") (pinfunction "OUT_7") (pintype "output"))
      (node (ref "R10") (pin "1") (pinfunction "1_1") (pintype "passive"))
    )
    (net (code "64") (name "Net-(IC3C-+IN)") (class "Default")
      (node (ref "IC3") (pin "12") (pinfunction "+IN_12") (pintype "input"))
      (node (ref "R28") (pin "1") (pinfunction "1_1") (pintype "passive"))
      (node (ref "S2") (pin "12") (pinfunction "12_12") (pintype "passive"))
    )
    (net (code "65") (name "Net-(IC3C--IN)") (class "Default")
      (node (ref "IC3") (pin "13") (pinfunction "-IN_13") (pintype "input"))
      (node (ref "IC3") (pin "14") (pinfunction "OUT_14") (pintype "output"))
      (node (ref "R12") (pin "1") (pinfunction "1_1") (pintype "passive"))
    )
    (net (code "66") (name "Net-(IC3D-+IN)") (class "Default")
      (node (ref "IC3") (pin "10") (pinfunction "+IN_10") (pintype "input"))
      (node (ref "R27") (pin "1") (pinfunction "1_1") (pintype "passive"))
      (node (ref "S2") (pin "11") (pinfunction "11_11") (pintype "passive"))
    )
    (net (code "67") (name "Net-(IC3D--IN)") (class "Default")
      (node (ref "IC3") (pin "8") (pinfunction "OUT_8") (pintype "output"))
      (node (ref "IC3") (pin "9") (pinfunction "-IN_9") (pintype "input"))
      (node (ref "R11") (pin "1") (pinfunction "1_1") (pintype "passive"))
    )
    (net (code "68") (name "Net-(IC4A-+IN)") (class "Default")
      (node (ref "IC4") (pin "3") (pinfunction "+IN_3") (pintype "input"))
      (node (ref "R29") (pin "1") (pinfunction "1_1") (pintype "passive"))
      (node (ref "S2") (pin "13") (pinfunction "13_13") (pintype "passive"))
    )
    (net (code "69") (name "Net-(IC4A--IN)") (class "Default")
      (node (ref "IC4") (pin "1") (pinfunction "OUT_1") (pintype "output"))
      (node (ref "IC4") (pin "2") (pinfunction "-IN_2") (pintype "input"))
      (node (ref "R13") (pin "1") (pinfunction "1_1") (pintype "passive"))
    )
    (net (code "70") (name "Net-(IC4B-+IN)") (class "Default")
      (node (ref "IC4") (pin "5") (pinfunction "+IN_5") (pintype "input"))
      (node (ref "R30") (pin "1") (pinfunction "1_1") (pintype "passive"))
      (node (ref "S2") (pin "14") (pinfunction "14_14") (pintype "passive"))
    )
    (net (code "71") (name "Net-(IC4B--IN)") (class "Default")
      (node (ref "IC4") (pin "6") (pinfunction "-IN_6") (pintype "input"))
      (node (ref "IC4") (pin "7") (pinfunction "OUT_7") (pintype "output"))
      (node (ref "R14") (pin "1") (pinfunction "1_1") (pintype "passive"))
    )
    (net (code "72") (name "Net-(IC4C-+IN)") (class "Default")
      (node (ref "IC4") (pin "12") (pinfunction "+IN_12") (pintype "input"))
      (node (ref "R32") (pin "1") (pinfunction "1_1") (pintype "passive"))
      (node (ref "S2") (pin "16") (pinfunction "16_16") (pintype "passive"))
    )
    (net (code "73") (name "Net-(IC4C--IN)") (class "Default")
      (node (ref "IC4") (pin "13") (pinfunction "-IN_13") (pintype "input"))
      (node (ref "IC4") (pin "14") (pinfunction "OUT_14") (pintype "output"))
      (node (ref "R16") (pin "1") (pinfunction "1_1") (pintype "passive"))
    )
    (net (code "74") (name "Net-(IC4D-+IN)") (class "Default")
      (node (ref "IC4") (pin "10") (pinfunction "+IN_10") (pintype "input"))
      (node (ref "R31") (pin "1") (pinfunction "1_1") (pintype "passive"))
      (node (ref "S2") (pin "15") (pinfunction "15_15") (pintype "passive"))
    )
    (net (code "75") (name "Net-(IC4D--IN)") (class "Default")
      (node (ref "IC4") (pin "8") (pinfunction "OUT_8") (pintype "output"))
      (node (ref "IC4") (pin "9") (pinfunction "-IN_9") (pintype "input"))
      (node (ref "R15") (pin "1") (pinfunction "1_1") (pintype "passive"))
    )
    (net (code "76") (name "Net-(IC5A-+IN)") (class "Default")
      (node (ref "IC5") (pin "3") (pinfunction "+IN_3") (pintype "input"))
      (node (ref "R55") (pin "2") (pinfunction "2_2") (pintype "passive"))
      (node (ref "R56") (pin "2") (pinfunction "2_2") (pintype "passive"))
    )
    (net (code "77") (name "Net-(IC5B-+IN)") (class "Default")
      (node (ref "IC5") (pin "5") (pinfunction "+IN_5") (pintype "input"))
      (node (ref "R71") (pin "2") (pinfunction "2_2") (pintype "passive"))
      (node (ref "R72") (pin "2") (pinfunction "2_2") (pintype "passive"))
    )
    (net (code "78") (name "Net-(IC5C-+IN)") (class "Default")
      (node (ref "IC5") (pin "10") (pinfunction "+IN_10") (pintype "input"))
      (node (ref "R69") (pin "2") (pinfunction "2_2") (pintype "passive"))
      (node (ref "R70") (pin "2") (pinfunction "2_2") (pintype "passive"))
    )
    (net (code "79") (name "Net-(IC5D-+IN)") (class "Default")
      (node (ref "IC5") (pin "12") (pinfunction "+IN_12") (pintype "input"))
      (node (ref "R53") (pin "2") (pinfunction "2_2") (pintype "passive"))
      (node (ref "R54") (pin "2") (pinfunction "2_2") (pintype "passive"))
    )
    (net (code "80") (name "Net-(IC6A-+IN)") (class "Default")
      (node (ref "IC6") (pin "3") (pinfunction "+IN_3") (pintype "input"))
      (node (ref "R59") (pin "2") (pinfunction "2_2") (pintype "passive"))
      (node (ref "R60") (pin "2") (pinfunction "2_2") (pintype "passive"))
    )
    (net (code "81") (name "Net-(IC6B-+IN)") (class "Default")
      (node (ref "IC6") (pin "5") (pinfunction "+IN_5") (pintype "input"))
      (node (ref "R75") (pin "2") (pinfunction "2_2") (pintype "passive"))
      (node (ref "R76") (pin "2") (pinfunction "2_2") (pintype "passive"))
    )
    (net (code "82") (name "Net-(IC6C-+IN)") (class "Default")
      (node (ref "IC6") (pin "10") (pinfunction "+IN_10") (pintype "input"))
      (node (ref "R73") (pin "2") (pinfunction "2_2") (pintype "passive"))
      (node (ref "R74") (pin "2") (pinfunction "2_2") (pintype "passive"))
    )
    (net (code "83") (name "Net-(IC6D-+IN)") (class "Default")
      (node (ref "IC6") (pin "12") (pinfunction "+IN_12") (pintype "input"))
      (node (ref "R57") (pin "2") (pinfunction "2_2") (pintype "passive"))
      (node (ref "R58") (pin "2") (pinfunction "2_2") (pintype "passive"))
    )
    (net (code "84") (name "Net-(IC7A-+IN)") (class "Default")
      (node (ref "IC7") (pin "3") (pinfunction "+IN_3") (pintype "input"))
      (node (ref "R63") (pin "2") (pinfunction "2_2") (pintype "passive"))
      (node (ref "R64") (pin "2") (pinfunction "2_2") (pintype "passive"))
    )
    (net (code "85") (name "Net-(IC7B-+IN)") (class "Default")
      (node (ref "IC7") (pin "5") (pinfunction "+IN_5") (pintype "input"))
      (node (ref "R79") (pin "2") (pinfunction "2_2") (pintype "passive"))
      (node (ref "R80") (pin "2") (pinfunction "2_2") (pintype "passive"))
    )
    (net (code "86") (name "Net-(IC7C-+IN)") (class "Default")
      (node (ref "IC7") (pin "10") (pinfunction "+IN_10") (pintype "input"))
      (node (ref "R77") (pin "2") (pinfunction "2_2") (pintype "passive"))
      (node (ref "R78") (pin "2") (pinfunction "2_2") (pintype "passive"))
    )
    (net (code "87") (name "Net-(IC7D-+IN)") (class "Default")
      (node (ref "IC7") (pin "12") (pinfunction "+IN_12") (pintype "input"))
      (node (ref "R61") (pin "2") (pinfunction "2_2") (pintype "passive"))
      (node (ref "R62") (pin "2") (pinfunction "2_2") (pintype "passive"))
    )
    (net (code "88") (name "Net-(IC8A-+IN)") (class "Default")
      (node (ref "IC8") (pin "3") (pinfunction "+IN_3") (pintype "input"))
      (node (ref "R51") (pin "2") (pinfunction "2_2") (pintype "passive"))
      (node (ref "R52") (pin "2") (pinfunction "2_2") (pintype "passive"))
    )
    (net (code "89") (name "Net-(IC8B-+IN)") (class "Default")
      (node (ref "IC8") (pin "5") (pinfunction "+IN_5") (pintype "input"))
      (node (ref "R67") (pin "2") (pinfunction "2_2") (pintype "passive"))
      (node (ref "R68") (pin "2") (pinfunction "2_2") (pintype "passive"))
    )
    (net (code "90") (name "Net-(IC8C-+IN)") (class "Default")
      (node (ref "IC8") (pin "10") (pinfunction "+IN_10") (pintype "input"))
      (node (ref "R81") (pin "2") (pinfunction "2_2") (pintype "passive"))
      (node (ref "R82") (pin "2") (pinfunction "2_2") (pintype "passive"))
    )
    (net (code "91") (name "Net-(JP2-LEFT)") (class "Default")
      (node (ref "JP2") (pin "P$1_TIP") (pinfunction "LEFT_P$1_TIP") (pintype "bidirectional"))
      (node (ref "S100") (pin "P2") (pinfunction "5_P2") (pintype "bidirectional"))
    )
    (net (code "92") (name "Net-(JP2-RIGHT)") (class "Default")
      (node (ref "JP2") (pin "P$2_SWITCH") (pinfunction "RIGHT_P$2_SWITCH") (pintype "bidirectional"))
      (node (ref "S100") (pin "P1") (pinfunction "2_P1") (pintype "bidirectional"))
    )
    (net (code "93") (name "Net-(LED1-PadA)") (class "Default")
      (node (ref "LED1") (pin "A") (pinfunction "A_A") (pintype "passive"))
      (node (ref "R84") (pin "1") (pinfunction "1_1") (pintype "passive"))
    )
    (net (code "94") (name "Net-(R33-Pad1)") (class "Default")
      (node (ref "R33") (pin "1") (pinfunction "1_1") (pintype "passive"))
      (node (ref "S1") (pin "8") (pinfunction "8_8") (pintype "passive"))
    )
    (net (code "95") (name "Net-(R34-Pad1)") (class "Default")
      (node (ref "R34") (pin "1") (pinfunction "1_1") (pintype "passive"))
      (node (ref "S1") (pin "7") (pinfunction "7_7") (pintype "passive"))
    )
    (net (code "96") (name "Net-(R35-Pad1)") (class "Default")
      (node (ref "R35") (pin "1") (pinfunction "1_1") (pintype "passive"))
      (node (ref "S1") (pin "6") (pinfunction "6_6") (pintype "passive"))
    )
    (net (code "97") (name "Net-(R36-Pad1)") (class "Default")
      (node (ref "R36") (pin "1") (pinfunction "1_1") (pintype "passive"))
      (node (ref "S1") (pin "5") (pinfunction "5_5") (pintype "passive"))
    )
    (net (code "98") (name "Net-(R37-Pad1)") (class "Default")
      (node (ref "R37") (pin "1") (pinfunction "1_1") (pintype "passive"))
      (node (ref "S1") (pin "4") (pinfunction "4_4") (pintype "passive"))
    )
    (net (code "99") (name "Net-(R38-Pad1)") (class "Default")
      (node (ref "R38") (pin "1") (pinfunction "1_1") (pintype "passive"))
      (node (ref "S1") (pin "3") (pinfunction "3_3") (pintype "passive"))
    )
    (net (code "100") (name "Net-(R39-Pad1)") (class "Default")
      (node (ref "R39") (pin "1") (pinfunction "1_1") (pintype "passive"))
      (node (ref "S1") (pin "2") (pinfunction "2_2") (pintype "passive"))
    )
    (net (code "101") (name "Net-(R40-Pad1)") (class "Default")
      (node (ref "R40") (pin "1") (pinfunction "1_1") (pintype "passive"))
      (node (ref "S1") (pin "1") (pinfunction "1_1") (pintype "passive"))
    )
    (net (code "102") (name "Net-(R41-Pad1)") (class "Default")
      (node (ref "R41") (pin "1") (pinfunction "1_1") (pintype "passive"))
      (node (ref "S2") (pin "8") (pinfunction "8_8") (pintype "passive"))
    )
    (net (code "103") (name "Net-(R42-Pad1)") (class "Default")
      (node (ref "R42") (pin "1") (pinfunction "1_1") (pintype "passive"))
      (node (ref "S2") (pin "7") (pinfunction "7_7") (pintype "passive"))
    )
    (net (code "104") (name "Net-(R43-Pad1)") (class "Default")
      (node (ref "R43") (pin "1") (pinfunction "1_1") (pintype "passive"))
      (node (ref "S2") (pin "6") (pinfunction "6_6") (pintype "passive"))
    )
    (net (code "105") (name "Net-(R44-Pad1)") (class "Default")
      (node (ref "R44") (pin "1") (pinfunction "1_1") (pintype "passive"))
      (node (ref "S2") (pin "5") (pinfunction "5_5") (pintype "passive"))
    )
    (net (code "106") (name "Net-(R45-Pad1)") (class "Default")
      (node (ref "R45") (pin "1") (pinfunction "1_1") (pintype "passive"))
      (node (ref "S2") (pin "4") (pinfunction "4_4") (pintype "passive"))
    )
    (net (code "107") (name "Net-(R46-Pad1)") (class "Default")
      (node (ref "R46") (pin "1") (pinfunction "1_1") (pintype "passive"))
      (node (ref "S2") (pin "3") (pinfunction "3_3") (pintype "passive"))
    )
    (net (code "108") (name "Net-(R47-Pad1)") (class "Default")
      (node (ref "R47") (pin "1") (pinfunction "1_1") (pintype "passive"))
      (node (ref "S2") (pin "2") (pinfunction "2_2") (pintype "passive"))
    )
    (net (code "109") (name "Net-(R48-Pad1)") (class "Default")
      (node (ref "R48") (pin "1") (pinfunction "1_1") (pintype "passive"))
      (node (ref "S2") (pin "1") (pinfunction "1_1") (pintype "passive"))
    )
    (net (code "110") (name "Net-(S100-1)") (class "Default")
      (node (ref "R85") (pin "1") (pinfunction "1_1") (pintype "passive"))
      (node (ref "S100") (pin "P1-TA") (pinfunction "1_P1-TA") (pintype "bidirectional"))
      (node (ref "S100") (pin "P2-TB") (pinfunction "6_P2-TB") (pintype "bidirectional"))
    )
    (net (code "111") (name "Net-(S100-3)") (class "Default")
      (node (ref "R83") (pin "1") (pinfunction "1_1") (pintype "passive"))
      (node (ref "S100") (pin "P1-TB") (pinfunction "3_P1-TB") (pintype "bidirectional"))
      (node (ref "S100") (pin "P2-TA") (pinfunction "4_P2-TA") (pintype "bidirectional"))
    )
    (net (code "112") (name "Net-(V1-BYPASS)") (class "Default")
      (node (ref "C3") (pin "1") (pinfunction "1_1") (pintype "passive"))
      (node (ref "V1") (pin "4") (pinfunction "BYPASS_4") (pintype "passive"))
    )
    (net (code "113") (name "Net-(V100-+VOUT)") (class "Default")
      (node (ref "D6") (pin "A") (pinfunction "A_A") (pintype "passive"))
      (node (ref "V100") (pin "4") (pinfunction "+VOUT_4") (pintype "passive"))
    )
    (net (code "114") (name "S$2") (class "Default")
      (node (ref "IC8") (pin "12") (pinfunction "+IN_12") (pintype "input"))
      (node (ref "R65") (pin "2") (pinfunction "2_2") (pintype "passive"))
      (node (ref "R66") (pin "2") (pinfunction "2_2") (pintype "passive"))
    )
    (net (code "115") (name "S0") (class "Default")
      (node (ref "IC10") (pin "8") (pinfunction "8/TX3_8") (pintype "bidirectional"))
      (node (ref "IC9") (pin "10") (pinfunction "S0_10") (pintype "input"))
    )
    (net (code "116") (name "S1") (class "Default")
      (node (ref "IC10") (pin "7") (pinfunction "7/RX3_7") (pintype "bidirectional"))
      (node (ref "IC9") (pin "11") (pinfunction "S1_11") (pintype "input"))
    )
    (net (code "117") (name "S2") (class "Default")
      (node (ref "IC10") (pin "6") (pinfunction "6/PWM_6") (pintype "bidirectional"))
      (node (ref "IC9") (pin "14") (pinfunction "S2_14") (pintype "input"))
    )
    (net (code "118") (name "S3") (class "Default")
      (node (ref "IC10") (pin "5") (pinfunction "5/PWM_5") (pintype "bidirectional"))
      (node (ref "IC9") (pin "13") (pinfunction "S3_13") (pintype "input"))
    )
    (net (code "119") (name "SCL") (class "Default")
      (node (ref "D2") (pin "A") (pinfunction "A_A") (pintype "passive"))
      (node (ref "D3") (pin "C") (pinfunction "C_C") (pintype "passive"))
      (node (ref "I2C") (pin "2") (pinfunction "2_2") (pintype "passive"))
      (node (ref "IC10") (pin "19/A5") (pinfunction "19/A5/T/SCL0_19/A5") (pintype "bidirectional"))
      (node (ref "JP1") (pin "P$2_SWITCH") (pinfunction "RIGHT_P$2_SWITCH") (pintype "bidirectional"))
      (node (ref "R49") (pin "1") (pinfunction "1_1") (pintype "passive"))
    )
    (net (code "120") (name "SDA") (class "Default")
      (node (ref "D4") (pin "C") (pinfunction "C_C") (pintype "passive"))
      (node (ref "D5") (pin "A") (pinfunction "A_A") (pintype "passive"))
      (node (ref "I2C") (pin "1") (pinfunction "1_1") (pintype "passive"))
      (node (ref "IC10") (pin "18/A4") (pinfunction "18/A4/T/SDA0_18/A4") (pintype "bidirectional"))
      (node (ref "JP1") (pin "P$1_TIP") (pinfunction "LEFT_P$1_TIP") (pintype "bidirectional"))
      (node (ref "R50") (pin "1") (pinfunction "1_1") (pintype "passive"))
    )
    (net (code "121") (name "W0") (class "Default")
      (node (ref "R17") (pin "2") (pinfunction "2_2") (pintype "passive"))
      (node (ref "R69") (pin "1") (pinfunction "1_1") (pintype "passive"))
      (node (ref "U$1") (pin "2") (pinfunction "2_2") (pintype "bidirectional"))
    )
    (net (code "122") (name "W1") (class "Default")
      (node (ref "R18") (pin "2") (pinfunction "2_2") (pintype "passive"))
      (node (ref "R53") (pin "1") (pinfunction "1_1") (pintype "passive"))
      (node (ref "U$2") (pin "2") (pinfunction "2_2") (pintype "bidirectional"))
    )
    (net (code "123") (name "W2") (class "Default")
      (node (ref "R19") (pin "2") (pinfunction "2_2") (pintype "passive"))
      (node (ref "R71") (pin "1") (pinfunction "1_1") (pintype "passive"))
      (node (ref "U$3") (pin "2") (pinfunction "2_2") (pintype "bidirectional"))
    )
    (net (code "124") (name "W3") (class "Default")
      (node (ref "R20") (pin "2") (pinfunction "2_2") (pintype "passive"))
      (node (ref "R55") (pin "1") (pinfunction "1_1") (pintype "passive"))
      (node (ref "U$4") (pin "2") (pinfunction "2_2") (pintype "bidirectional"))
    )
    (net (code "125") (name "W4") (class "Default")
      (node (ref "R21") (pin "2") (pinfunction "2_2") (pintype "passive"))
      (node (ref "R73") (pin "1") (pinfunction "1_1") (pintype "passive"))
      (node (ref "U$5") (pin "2") (pinfunction "2_2") (pintype "bidirectional"))
    )
    (net (code "126") (name "W5") (class "Default")
      (node (ref "R22") (pin "2") (pinfunction "2_2") (pintype "passive"))
      (node (ref "R57") (pin "1") (pinfunction "1_1") (pintype "passive"))
      (node (ref "U$6") (pin "2") (pinfunction "2_2") (pintype "bidirectional"))
    )
    (net (code "127") (name "W6") (class "Default")
      (node (ref "R23") (pin "2") (pinfunction "2_2") (pintype "passive"))
      (node (ref "R75") (pin "1") (pinfunction "1_1") (pintype "passive"))
      (node (ref "U$7") (pin "2") (pinfunction "2_2") (pintype "bidirectional"))
    )
    (net (code "128") (name "W7") (class "Default")
      (node (ref "R24") (pin "2") (pinfunction "2_2") (pintype "passive"))
      (node (ref "R59") (pin "1") (pinfunction "1_1") (pintype "passive"))
      (node (ref "U$8") (pin "2") (pinfunction "2_2") (pintype "bidirectional"))
    )
    (net (code "129") (name "W8") (class "Default")
      (node (ref "R25") (pin "2") (pinfunction "2_2") (pintype "passive"))
      (node (ref "R77") (pin "1") (pinfunction "1_1") (pintype "passive"))
      (node (ref "U$9") (pin "2") (pinfunction "2_2") (pintype "bidirectional"))
    )
    (net (code "130") (name "W9") (class "Default")
      (node (ref "R26") (pin "2") (pinfunction "2_2") (pintype "passive"))
      (node (ref "R61") (pin "1") (pinfunction "1_1") (pintype "passive"))
      (node (ref "U$10") (pin "2") (pinfunction "2_2") (pintype "bidirectional"))
    )
    (net (code "131") (name "W10") (class "Default")
      (node (ref "R27") (pin "2") (pinfunction "2_2") (pintype "passive"))
      (node (ref "R79") (pin "1") (pinfunction "1_1") (pintype "passive"))
      (node (ref "U$11") (pin "2") (pinfunction "2_2") (pintype "bidirectional"))
    )
    (net (code "132") (name "W11") (class "Default")
      (node (ref "R28") (pin "2") (pinfunction "2_2") (pintype "passive"))
      (node (ref "R63") (pin "1") (pinfunction "1_1") (pintype "passive"))
      (node (ref "U$12") (pin "2") (pinfunction "2_2") (pintype "bidirectional"))
    )
    (net (code "133") (name "W12") (class "Default")
      (node (ref "R29") (pin "2") (pinfunction "2_2") (pintype "passive"))
      (node (ref "R81") (pin "1") (pinfunction "1_1") (pintype "passive"))
      (node (ref "U$13") (pin "2") (pinfunction "2_2") (pintype "bidirectional"))
    )
    (net (code "134") (name "W13") (class "Default")
      (node (ref "R30") (pin "2") (pinfunction "2_2") (pintype "passive"))
      (node (ref "R65") (pin "1") (pinfunction "1_1") (pintype "passive"))
      (node (ref "U$14") (pin "2") (pinfunction "2_2") (pintype "bidirectional"))
    )
    (net (code "135") (name "W14") (class "Default")
      (node (ref "R31") (pin "2") (pinfunction "2_2") (pintype "passive"))
      (node (ref "R67") (pin "1") (pinfunction "1_1") (pintype "passive"))
      (node (ref "U$15") (pin "2") (pinfunction "2_2") (pintype "bidirectional"))
    )
    (net (code "136") (name "W15") (class "Default")
      (node (ref "R32") (pin "2") (pinfunction "2_2") (pintype "passive"))
      (node (ref "R51") (pin "1") (pinfunction "1_1") (pintype "passive"))
      (node (ref "U$16") (pin "2") (pinfunction "2_2") (pintype "bidirectional"))
    )
    (net (code "137") (name "unconnected-(IC10-0{slash}RX1{slash}T-Pad0)") (class "Default")
      (node (ref "IC10") (pin "0") (pinfunction "0/RX1/T_0") (pintype "bidirectional"))
    )
    (net (code "138") (name "unconnected-(IC10-3{slash}CAN-TX{slash}PWM-Pad3)") (class "Default")
      (node (ref "IC10") (pin "3") (pinfunction "3/CAN-TX/PWM_3") (pintype "bidirectional"))
    )
    (net (code "139") (name "unconnected-(IC10-4{slash}CAN-RX{slash}PWM-Pad4)") (class "Default")
      (node (ref "IC10") (pin "4") (pinfunction "4/CAN-RX/PWM_4") (pintype "bidirectional"))
    )
    (net (code "140") (name "unconnected-(IC10-9{slash}RX2{slash}PWM-Pad9)") (class "Default")
      (node (ref "IC10") (pin "9") (pinfunction "9/RX2/PWM_9") (pintype "bidirectional"))
    )
    (net (code "141") (name "unconnected-(IC10-10{slash}TX2{slash}PWM-Pad10)") (class "Default")
      (node (ref "IC10") (pin "10") (pinfunction "10/TX2/PWM_10") (pintype "bidirectional"))
    )
    (net (code "142") (name "unconnected-(IC10-11{slash}MOSI-Pad11)") (class "Default")
      (node (ref "IC10") (pin "11") (pinfunction "11/MOSI_11") (pintype "bidirectional"))
    )
    (net (code "143") (name "unconnected-(IC10-12{slash}MISO-Pad12)") (class "Default")
      (node (ref "IC10") (pin "12") (pinfunction "12/MISO_12") (pintype "bidirectional"))
    )
    (net (code "144") (name "unconnected-(IC10-13{slash}SCK{slash}LED-Pad13)") (class "Default")
      (node (ref "IC10") (pin "13") (pinfunction "13/SCK/LED_13") (pintype "bidirectional"))
    )
    (net (code "145") (name "unconnected-(IC10-15{slash}A1{slash}T-Pad15{slash}A1)") (class "Default")
      (node (ref "IC10") (pin "15/A1") (pinfunction "15/A1/T_15/A1") (pintype "bidirectional"))
    )
    (net (code "146") (name "unconnected-(IC10-16{slash}A2{slash}T-Pad16{slash}A2)") (class "Default")
      (node (ref "IC10") (pin "16/A2") (pinfunction "16/A2/T_16/A2") (pintype "bidirectional"))
    )
    (net (code "147") (name "unconnected-(IC10-17{slash}A3{slash}T-Pad17{slash}A3)") (class "Default")
      (node (ref "IC10") (pin "17/A3") (pinfunction "17/A3/T_17/A3") (pintype "bidirectional"))
    )
    (net (code "148") (name "unconnected-(IC10-20{slash}A6{slash}PWM-Pad20{slash}A6)") (class "Default")
      (node (ref "IC10") (pin "20/A6") (pinfunction "20/A6/PWM_20/A6") (pintype "bidirectional"))
    )
    (net (code "149") (name "unconnected-(IC10-21{slash}A7{slash}PWM-Pad21{slash}A7)") (class "Default")
      (node (ref "IC10") (pin "21/A7") (pinfunction "21/A7/PWM_21/A7") (pintype "bidirectional"))
    )
    (net (code "150") (name "unconnected-(IC10-22{slash}A8{slash}T{slash}PWM-Pad22{slash}A8)") (class "Default")
      (node (ref "IC10") (pin "22/A8") (pinfunction "22/A8/T/PWM_22/A8") (pintype "bidirectional"))
    )
    (net (code "151") (name "unconnected-(IC10-23{slash}A9{slash}T{slash}PWM-Pad23{slash}A9)") (class "Default")
      (node (ref "IC10") (pin "23/A9") (pinfunction "23/A9/T/PWM_23/A9") (pintype "bidirectional"))
    )
    (net (code "152") (name "unconnected-(IC10-Pad2)") (class "Default")
      (node (ref "IC10") (pin "2") (pinfunction "2_2") (pintype "bidirectional"))
    )
    (net (code "153") (name "unconnected-(J1-SWITCH-PadP$2_SWITCH)") (class "Default")
      (node (ref "J1") (pin "P$2_SWITCH") (pinfunction "SWITCH_P$2_SWITCH") (pintype "passive"))
    )
    (net (code "154") (name "unconnected-(J2-SWITCH-PadP$2_SWITCH)") (class "Default")
      (node (ref "J2") (pin "P$2_SWITCH") (pinfunction "SWITCH_P$2_SWITCH") (pintype "passive"))
    )
    (net (code "155") (name "unconnected-(J3-SWITCH-PadP$2_SWITCH)") (class "Default")
      (node (ref "J3") (pin "P$2_SWITCH") (pinfunction "SWITCH_P$2_SWITCH") (pintype "passive"))
    )
    (net (code "156") (name "unconnected-(J4-SWITCH-PadP$2_SWITCH)") (class "Default")
      (node (ref "J4") (pin "P$2_SWITCH") (pinfunction "SWITCH_P$2_SWITCH") (pintype "passive"))
    )
    (net (code "157") (name "unconnected-(J5-SWITCH-PadP$2_SWITCH)") (class "Default")
      (node (ref "J5") (pin "P$2_SWITCH") (pinfunction "SWITCH_P$2_SWITCH") (pintype "passive"))
    )
    (net (code "158") (name "unconnected-(J6-SWITCH-PadP$2_SWITCH)") (class "Default")
      (node (ref "J6") (pin "P$2_SWITCH") (pinfunction "SWITCH_P$2_SWITCH") (pintype "passive"))
    )
    (net (code "159") (name "unconnected-(J7-SWITCH-PadP$2_SWITCH)") (class "Default")
      (node (ref "J7") (pin "P$2_SWITCH") (pinfunction "SWITCH_P$2_SWITCH") (pintype "passive"))
    )
    (net (code "160") (name "unconnected-(J8-SWITCH-PadP$2_SWITCH)") (class "Default")
      (node (ref "J8") (pin "P$2_SWITCH") (pinfunction "SWITCH_P$2_SWITCH") (pintype "passive"))
    )
    (net (code "161") (name "unconnected-(J9-SWITCH-PadP$2_SWITCH)") (class "Default")
      (node (ref "J9") (pin "P$2_SWITCH") (pinfunction "SWITCH_P$2_SWITCH") (pintype "passive"))
    )
    (net (code "162") (name "unconnected-(J10-SWITCH-PadP$2_SWITCH)") (class "Default")
      (node (ref "J10") (pin "P$2_SWITCH") (pinfunction "SWITCH_P$2_SWITCH") (pintype "passive"))
    )
    (net (code "163") (name "unconnected-(J11-SWITCH-PadP$2_SWITCH)") (class "Default")
      (node (ref "J11") (pin "P$2_SWITCH") (pinfunction "SWITCH_P$2_SWITCH") (pintype "passive"))
    )
    (net (code "164") (name "unconnected-(J12-SWITCH-PadP$2_SWITCH)") (class "Default")
      (node (ref "J12") (pin "P$2_SWITCH") (pinfunction "SWITCH_P$2_SWITCH") (pintype "passive"))
    )
    (net (code "165") (name "unconnected-(J13-SWITCH-PadP$2_SWITCH)") (class "Default")
      (node (ref "J13") (pin "P$2_SWITCH") (pinfunction "SWITCH_P$2_SWITCH") (pintype "passive"))
    )
    (net (code "166") (name "unconnected-(J14-SWITCH-PadP$2_SWITCH)") (class "Default")
      (node (ref "J14") (pin "P$2_SWITCH") (pinfunction "SWITCH_P$2_SWITCH") (pintype "passive"))
    )
    (net (code "167") (name "unconnected-(J15-SWITCH-PadP$2_SWITCH)") (class "Default")
      (node (ref "J15") (pin "P$2_SWITCH") (pinfunction "SWITCH_P$2_SWITCH") (pintype "passive"))
    )
    (net (code "168") (name "unconnected-(J16-SWITCH-PadP$2_SWITCH)") (class "Default")
      (node (ref "J16") (pin "P$2_SWITCH") (pinfunction "SWITCH_P$2_SWITCH") (pintype "passive"))
    )
    (net (code "169") (name "unconnected-(S101-3-PadP1-TB)") (class "Default")
      (node (ref "S101") (pin "P1-TB") (pinfunction "3_P1-TB") (pintype "bidirectional"))
    )
    (net (code "170") (name "unconnected-(SV100-Pad1)") (class "Default")
      (node (ref "SV100") (pin "1") (pinfunction "1_1") (pintype "passive"))
    )
    (net (code "171") (name "unconnected-(SV100-Pad2)") (class "Default")
      (node (ref "SV100") (pin "2") (pinfunction "2_2") (pintype "passive"))
    )
  )
)
